# Roland_mem3.net
KiCad netlist of a schematic drawn in EAGLE
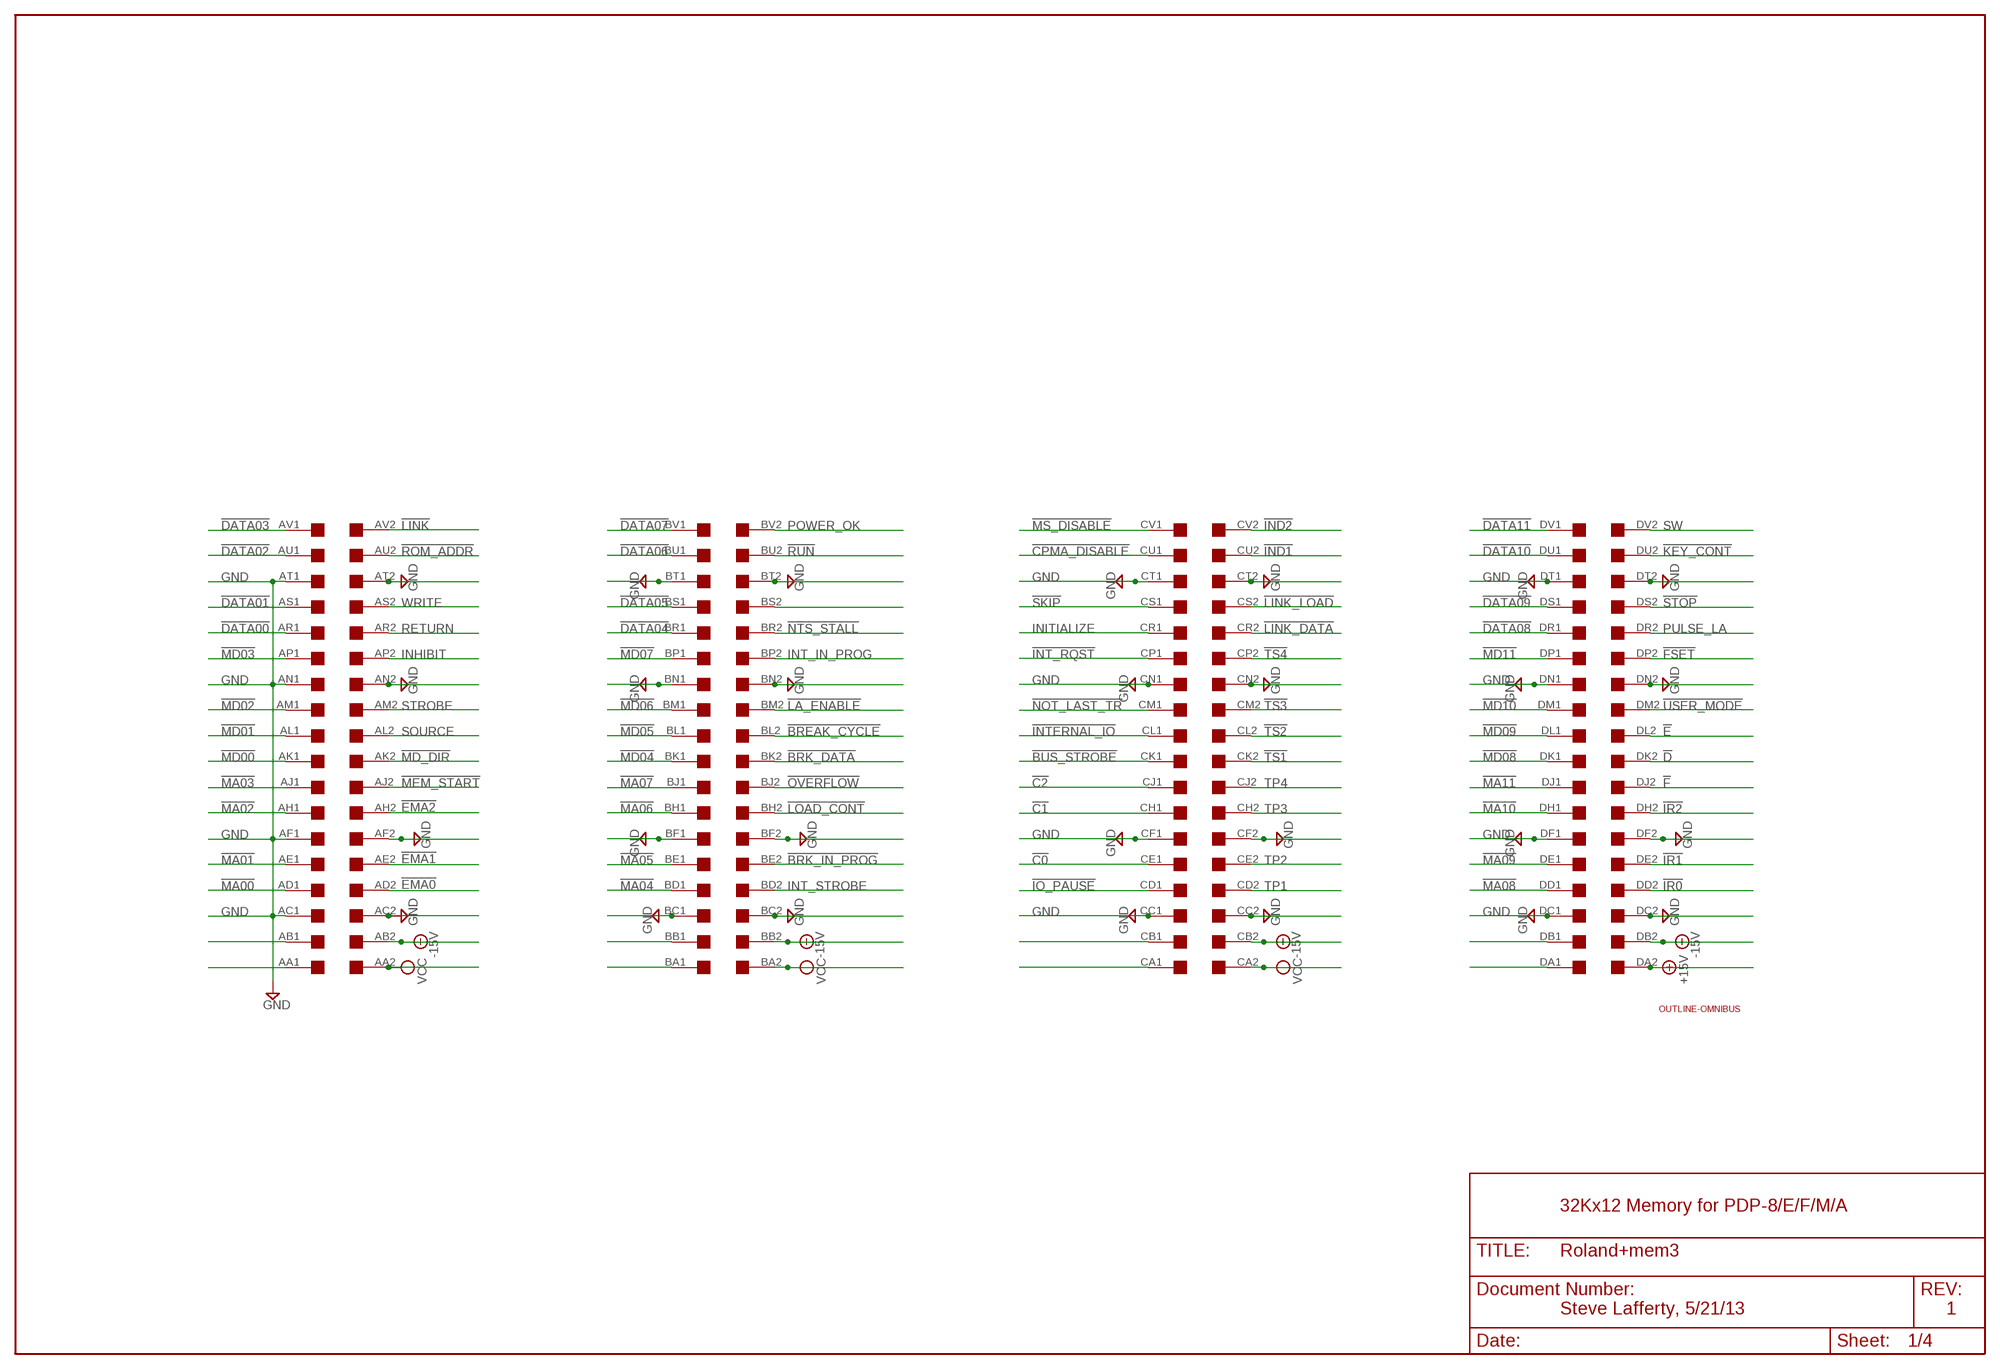
[diagram p0: schematic, sheet 1]
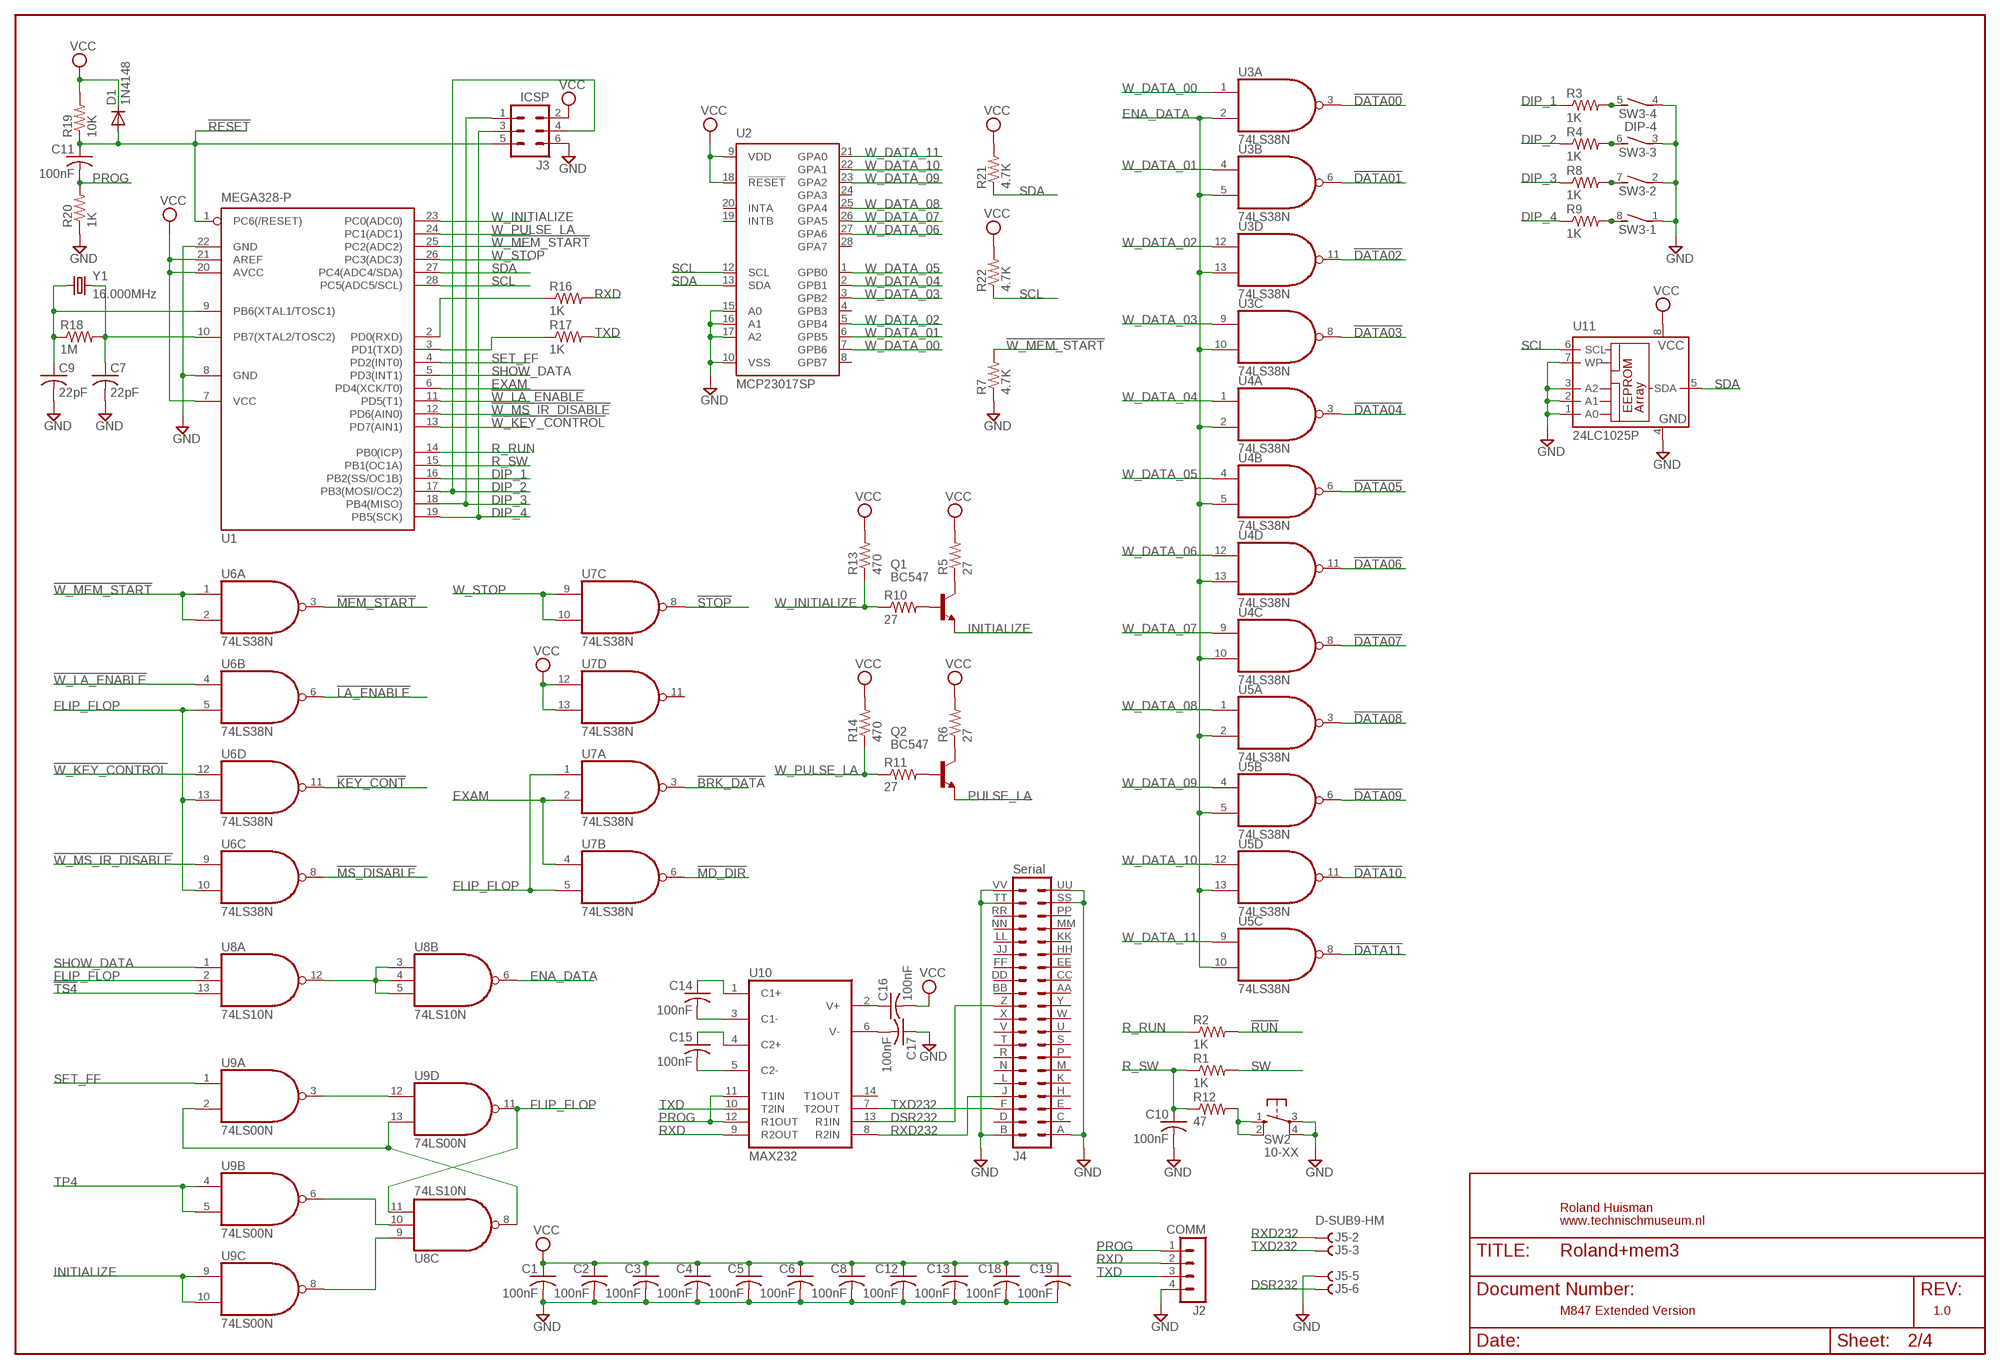
[diagram p1: schematic, sheet 2]
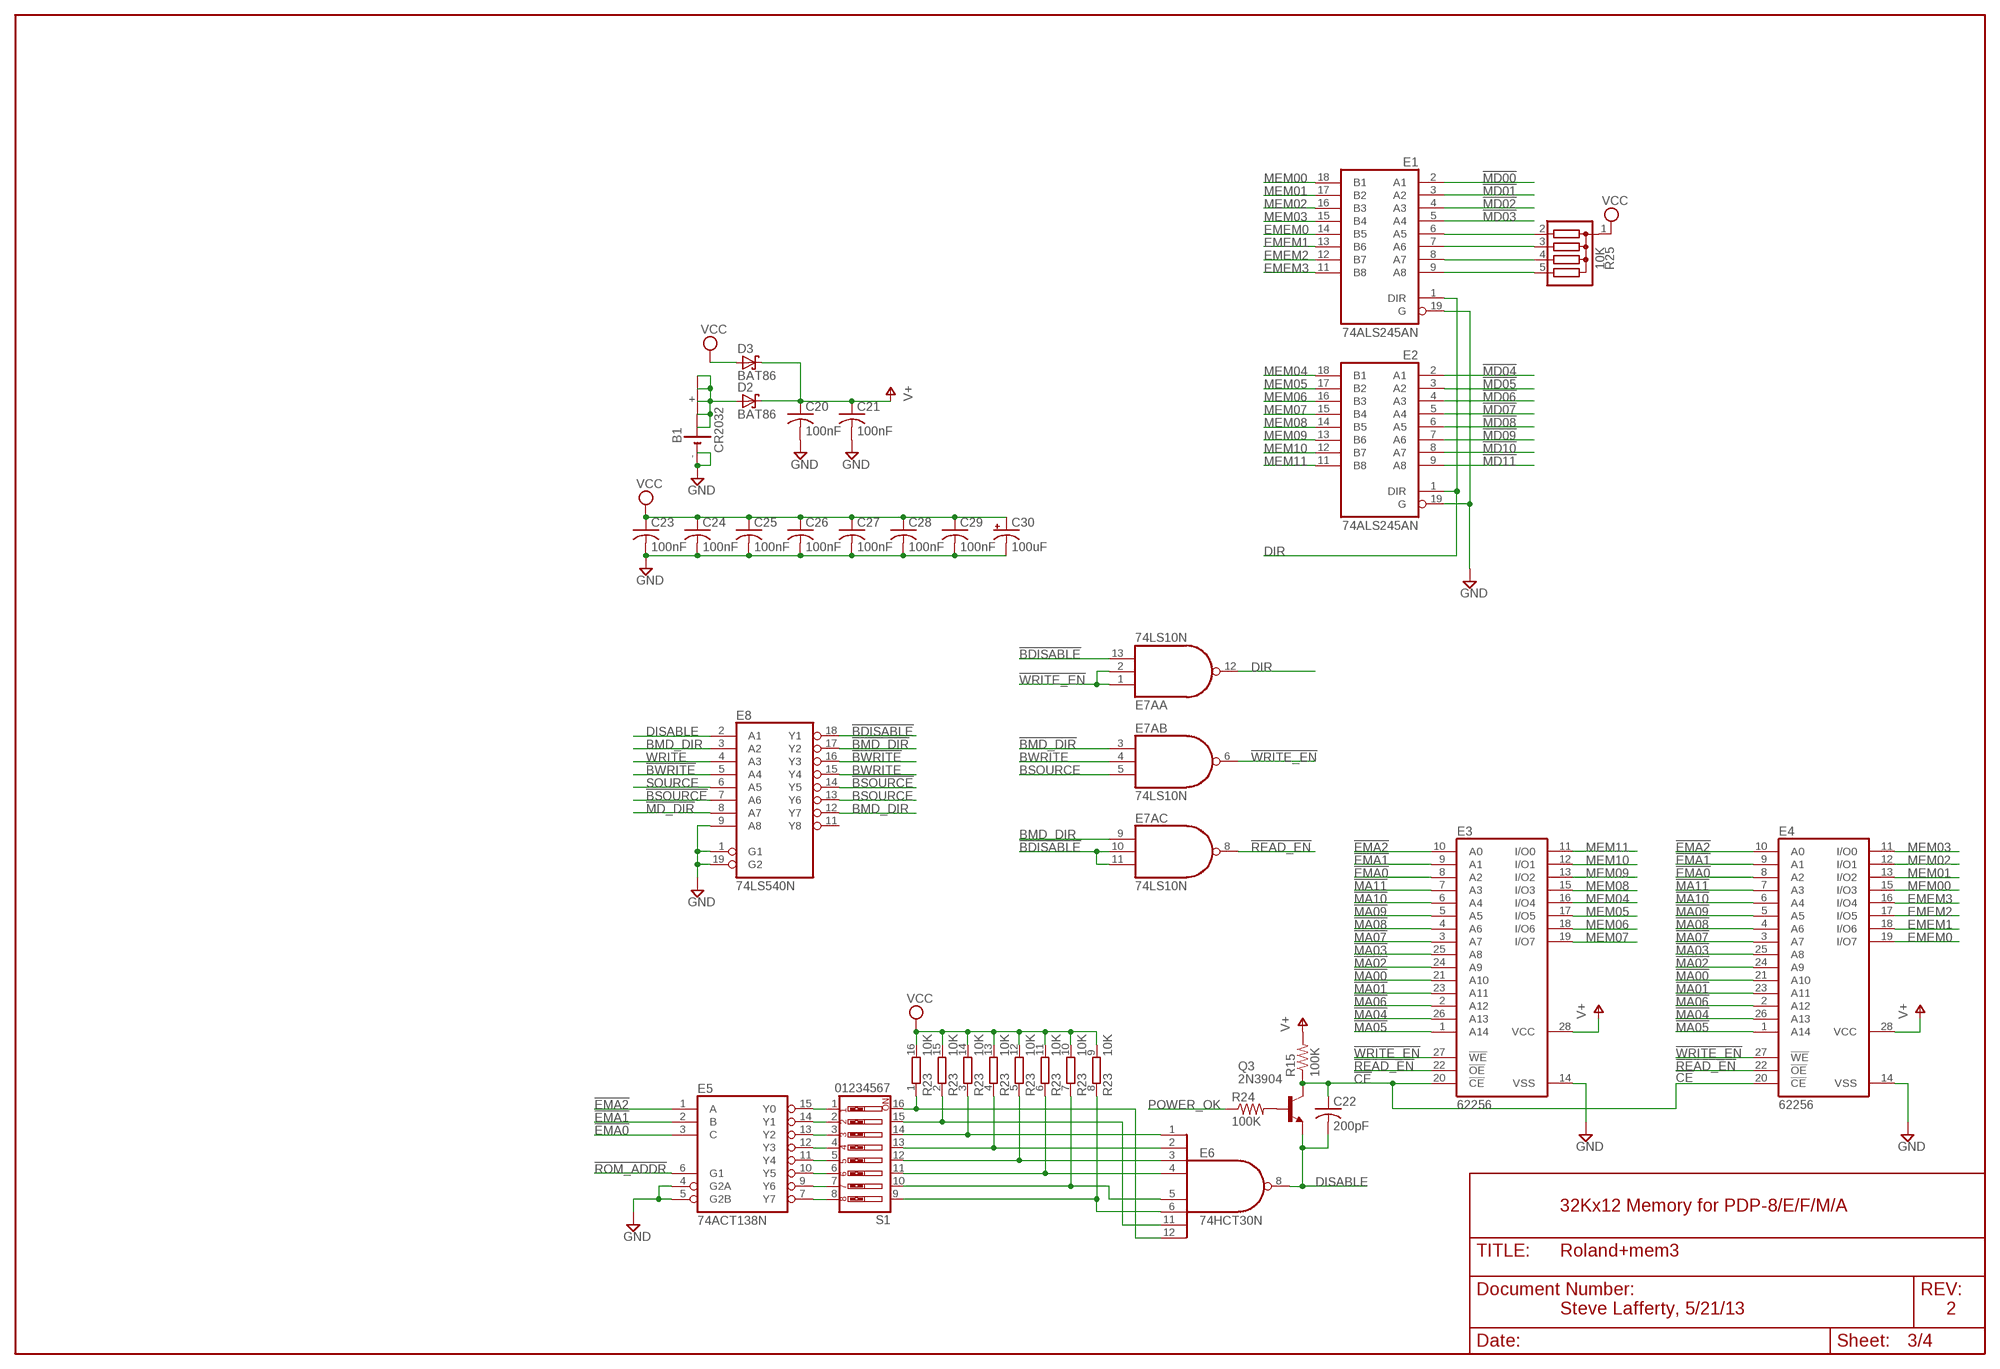
[diagram p2: schematic, sheet 3]
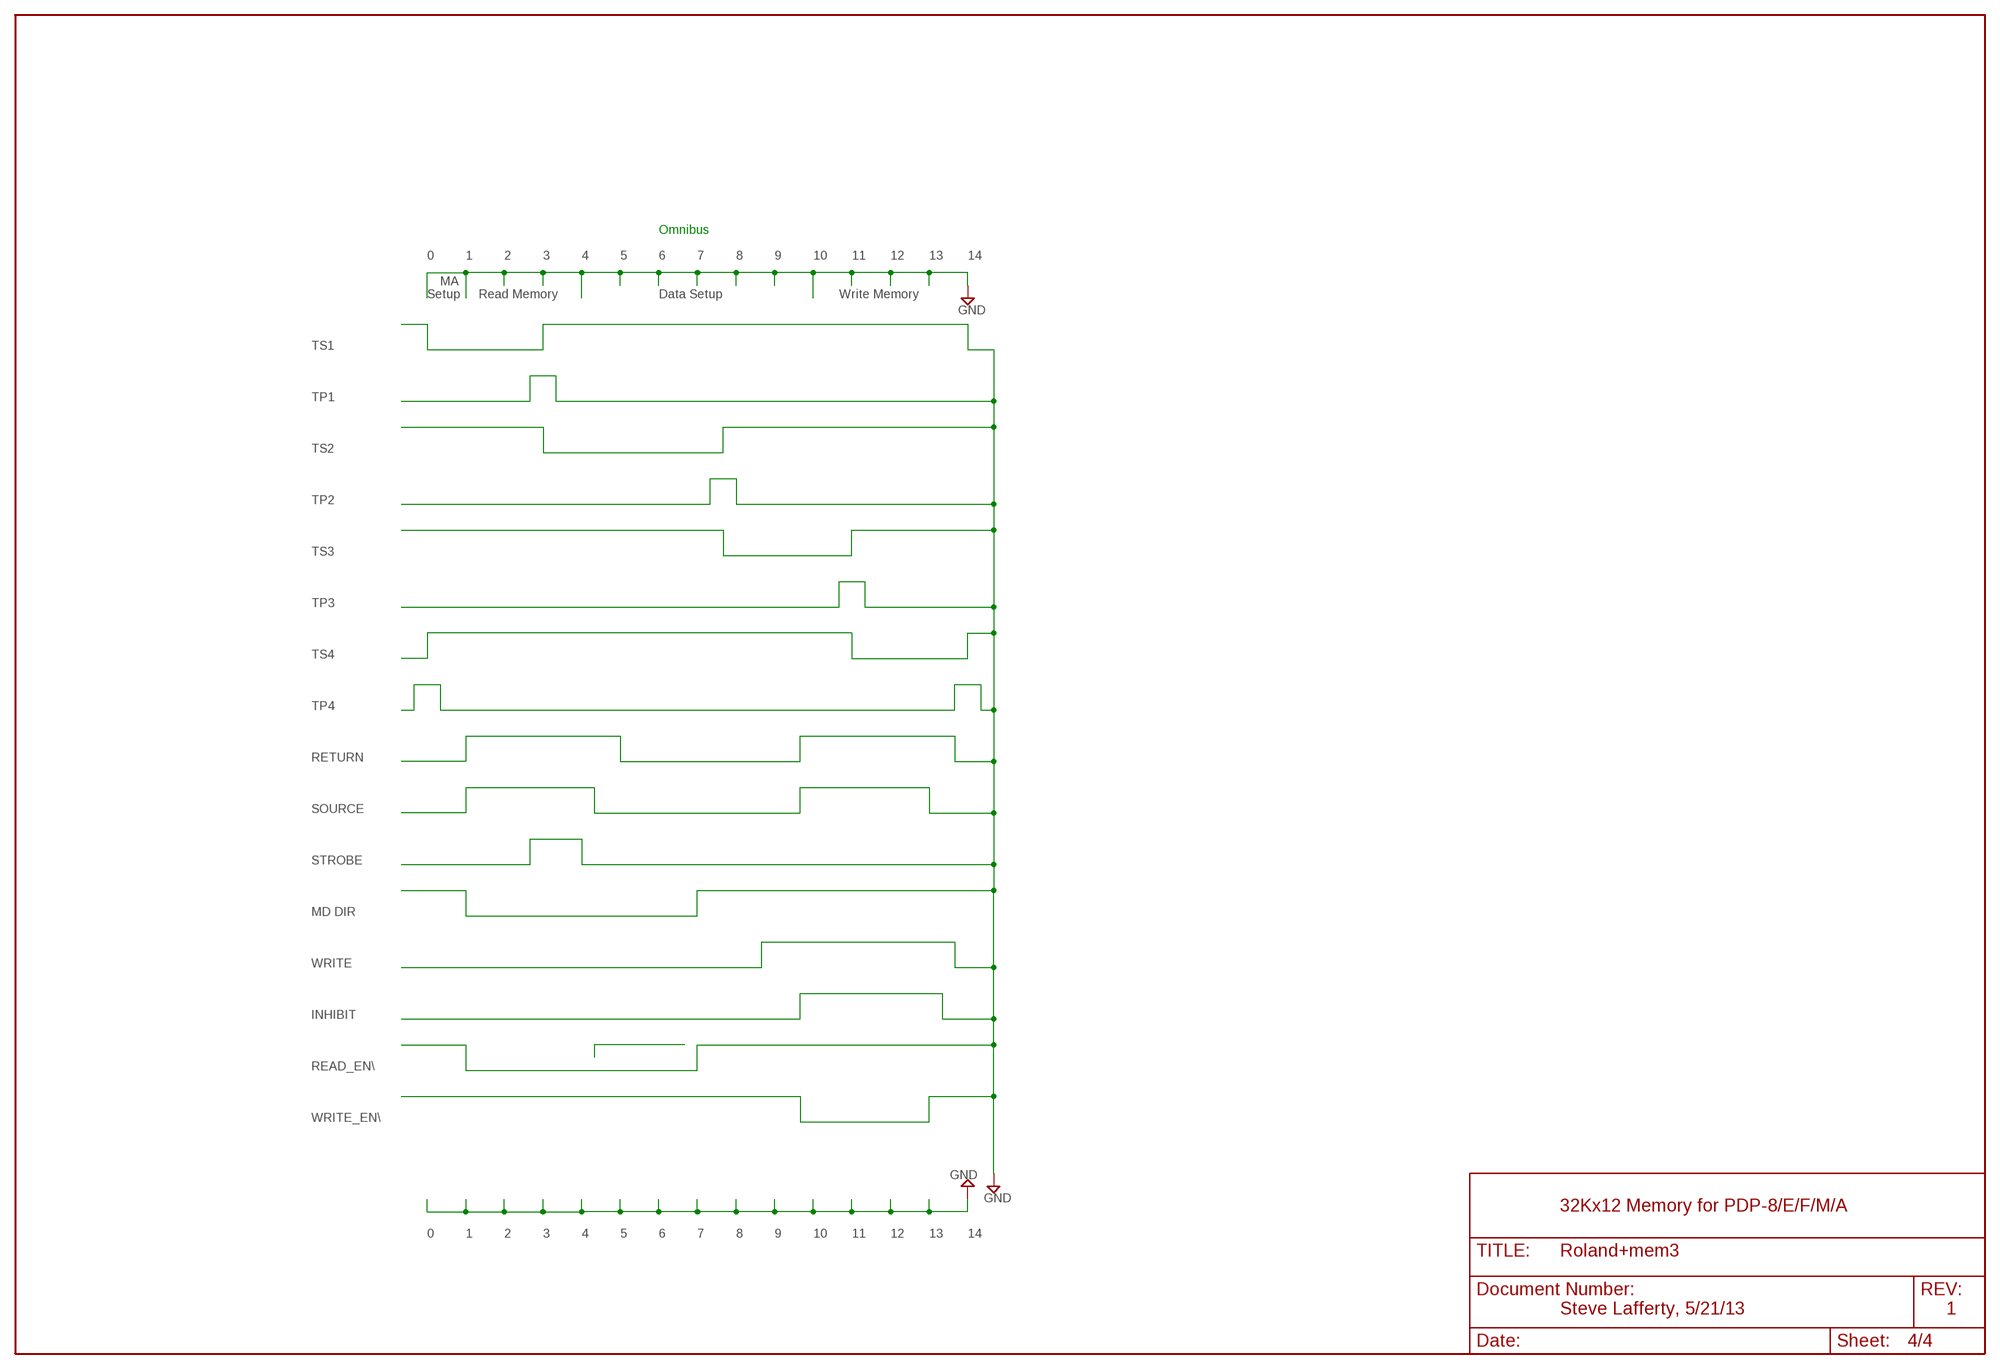
[diagram p3: schematic, sheet 4]

(export (version "E")
  (design (tool "Eeschema 10.0.6"))
  (components
    (comp (ref "J1")
      (value "EDGE")
      (footprint "eagle-import:EDGE-CON8")
      (libsource (lib "eagle-import") (part "QUAD"))
    )
    (comp (ref "U$1")
      (value "OUTLINE-OMNIBUS")
      (footprint "eagle-import:OMNIBUS")
      (libsource (lib "eagle-import") (part "OUTLINE-OMNIBUS"))
    )
    (comp (ref "C1")
      (value "100nF")
      (footprint "eagle-import:C050-025X075")
      (libsource (lib "eagle-import") (part "C-US050-025X075"))
    )
    (comp (ref "C2")
      (value "100nF")
      (footprint "eagle-import:C050-025X075")
      (libsource (lib "eagle-import") (part "C-US050-025X075"))
    )
    (comp (ref "C3")
      (value "100nF")
      (footprint "eagle-import:C050-025X075")
      (libsource (lib "eagle-import") (part "C-US050-025X075"))
    )
    (comp (ref "C4")
      (value "100nF")
      (footprint "eagle-import:C050-025X075")
      (libsource (lib "eagle-import") (part "C-US050-025X075"))
    )
    (comp (ref "C5")
      (value "100nF")
      (footprint "eagle-import:C050-025X075")
      (libsource (lib "eagle-import") (part "C-US050-025X075"))
    )
    (comp (ref "C6")
      (value "100nF")
      (footprint "eagle-import:C050-025X075")
      (libsource (lib "eagle-import") (part "C-US050-025X075"))
    )
    (comp (ref "C7")
      (value "22pF")
      (footprint "eagle-import:C050-025X075")
      (libsource (lib "eagle-import") (part "C-US050-025X075"))
    )
    (comp (ref "C8")
      (value "100nF")
      (footprint "eagle-import:C050-025X075")
      (libsource (lib "eagle-import") (part "C-US050-025X075"))
    )
    (comp (ref "C9")
      (value "22pF")
      (footprint "eagle-import:C050-025X075")
      (libsource (lib "eagle-import") (part "C-US050-025X075"))
    )
    (comp (ref "C10")
      (value "100nF")
      (footprint "eagle-import:C050-025X075")
      (libsource (lib "eagle-import") (part "C-US050-025X075"))
    )
    (comp (ref "C11")
      (value "100nF")
      (footprint "eagle-import:C050-025X075")
      (libsource (lib "eagle-import") (part "C-US050-025X075"))
    )
    (comp (ref "C12")
      (value "100nF")
      (footprint "eagle-import:C050-025X075")
      (libsource (lib "eagle-import") (part "C-US050-025X075"))
    )
    (comp (ref "C13")
      (value "100nF")
      (footprint "eagle-import:C050-025X075")
      (libsource (lib "eagle-import") (part "C-US050-025X075"))
    )
    (comp (ref "C14")
      (value "100nF")
      (footprint "eagle-import:C050-025X075")
      (libsource (lib "eagle-import") (part "C-US050-025X075"))
    )
    (comp (ref "C15")
      (value "100nF")
      (footprint "eagle-import:C050-025X075")
      (libsource (lib "eagle-import") (part "C-US050-025X075"))
    )
    (comp (ref "C16")
      (value "100nF")
      (footprint "eagle-import:C050-025X075")
      (libsource (lib "eagle-import") (part "C-US050-025X075"))
    )
    (comp (ref "C17")
      (value "100nF")
      (footprint "eagle-import:C050-025X075")
      (libsource (lib "eagle-import") (part "C-US050-025X075"))
    )
    (comp (ref "C18")
      (value "100nF")
      (footprint "eagle-import:C050-025X075")
      (libsource (lib "eagle-import") (part "C-US050-025X075"))
    )
    (comp (ref "C19")
      (value "100nF")
      (footprint "eagle-import:C050-025X075")
      (libsource (lib "eagle-import") (part "C-US050-025X075"))
    )
    (comp (ref "D1")
      (value "1N4148")
      (footprint "eagle-import:DO35-10")
      (libsource (lib "eagle-import") (part "1N4148DO35-10"))
    )
    (comp (ref "J2")
      (value "COMM")
      (footprint "eagle-import:MA04-1")
      (libsource (lib "eagle-import") (part "MA04-1"))
    )
    (comp (ref "J3")
      (value "ICSP")
      (footprint "eagle-import:MA03-2")
      (libsource (lib "eagle-import") (part "MA03-2"))
    )
    (comp (ref "J4")
      (value "Serial")
      (footprint "eagle-import:DEC40PINH")
      (libsource (lib "eagle-import") (part "DEC40PINH"))
    )
    (comp (ref "J5")
      (value "D-SUB9-HM")
      (footprint "eagle-import:H5M09RA")
      (libsource (lib "eagle-import") (part "D-SUB9-H5M09RA"))
    )
    (comp (ref "Q1")
      (value "BC547")
      (footprint "eagle-import:TO5")
      (libsource (lib "eagle-import") (part "-NPN-TO5"))
    )
    (comp (ref "Q2")
      (value "BC547")
      (footprint "eagle-import:TO5")
      (libsource (lib "eagle-import") (part "-NPN-TO5"))
    )
    (comp (ref "R1")
      (value "1K")
      (footprint "eagle-import:0207_10")
      (libsource (lib "eagle-import") (part "R-US_0207/10"))
    )
    (comp (ref "R2")
      (value "1K")
      (footprint "eagle-import:0207_10")
      (libsource (lib "eagle-import") (part "R-US_0207/10"))
    )
    (comp (ref "R3")
      (value "1K")
      (footprint "eagle-import:0207_10")
      (libsource (lib "eagle-import") (part "R-US_0207/10"))
    )
    (comp (ref "R4")
      (value "1K")
      (footprint "eagle-import:0207_10")
      (libsource (lib "eagle-import") (part "R-US_0207/10"))
    )
    (comp (ref "R5")
      (value "27")
      (footprint "eagle-import:0207_10")
      (libsource (lib "eagle-import") (part "R-US_0207/10"))
    )
    (comp (ref "R6")
      (value "27")
      (footprint "eagle-import:0207_10")
      (libsource (lib "eagle-import") (part "R-US_0207/10"))
    )
    (comp (ref "R7")
      (value "4.7K")
      (footprint "eagle-import:0207_10")
      (libsource (lib "eagle-import") (part "R-US_0207/10"))
    )
    (comp (ref "R8")
      (value "1K")
      (footprint "eagle-import:0207_10")
      (libsource (lib "eagle-import") (part "R-US_0207/10"))
    )
    (comp (ref "R9")
      (value "1K")
      (footprint "eagle-import:0207_10")
      (libsource (lib "eagle-import") (part "R-US_0207/10"))
    )
    (comp (ref "R10")
      (value "27")
      (footprint "eagle-import:0207_10")
      (libsource (lib "eagle-import") (part "R-US_0207/10"))
    )
    (comp (ref "R11")
      (value "27")
      (footprint "eagle-import:0207_10")
      (libsource (lib "eagle-import") (part "R-US_0207/10"))
    )
    (comp (ref "R12")
      (value "47")
      (footprint "eagle-import:0207_10")
      (libsource (lib "eagle-import") (part "R-US_0207/10"))
    )
    (comp (ref "R13")
      (value "470")
      (footprint "eagle-import:0207_10")
      (libsource (lib "eagle-import") (part "R-US_0207/10"))
    )
    (comp (ref "R14")
      (value "470")
      (footprint "eagle-import:0207_10")
      (libsource (lib "eagle-import") (part "R-US_0207/10"))
    )
    (comp (ref "R16")
      (value "1K")
      (footprint "eagle-import:0207_10")
      (libsource (lib "eagle-import") (part "R-US_0207/10"))
    )
    (comp (ref "R17")
      (value "1K")
      (footprint "eagle-import:0207_10")
      (libsource (lib "eagle-import") (part "R-US_0207/10"))
    )
    (comp (ref "R18")
      (value "1M")
      (footprint "eagle-import:0207_10")
      (libsource (lib "eagle-import") (part "R-US_0207/10"))
    )
    (comp (ref "R19")
      (value "10K")
      (footprint "eagle-import:0207_10")
      (libsource (lib "eagle-import") (part "R-US_0207/10"))
    )
    (comp (ref "R20")
      (value "1K")
      (footprint "eagle-import:0207_10")
      (libsource (lib "eagle-import") (part "R-US_0207/10"))
    )
    (comp (ref "R21")
      (value "4.7K")
      (footprint "eagle-import:0207_10")
      (libsource (lib "eagle-import") (part "R-US_0207/10"))
    )
    (comp (ref "R22")
      (value "4.7K")
      (footprint "eagle-import:0207_10")
      (libsource (lib "eagle-import") (part "R-US_0207/10"))
    )
    (comp (ref "SW2")
      (value "10-XX")
      (footprint "eagle-import:B3F-10XX")
      (fields (field (name "MPN") "B3F-1000"))
      (libsource (lib "eagle-import") (part "10-XX"))
    )
    (comp (ref "SW3")
      (value "DIP-4")
      (footprint "eagle-import:DIP04S")
      (libsource (lib "eagle-import") (part "DIP04S"))
    )
    (comp (ref "U1")
      (value "MEGA328-P")
      (footprint "eagle-import:DIL28-3")
      (libsource (lib "eagle-import") (part "MEGA8-P"))
    )
    (comp (ref "U2")
      (value "MCP23017SP")
      (footprint "eagle-import:DIL28-3")
      (fields (field (name "MF") "MICROCHIP") (field (name "MPN") "MCP23017-E/SP"))
      (libsource (lib "eagle-import") (part "MCP23017SP"))
    )
    (comp (ref "U3")
      (value "74LS38N")
      (footprint "eagle-import:DIL14")
      (libsource (lib "eagle-import") (part "7438NLS"))
    )
    (comp (ref "U4")
      (value "74LS38N")
      (footprint "eagle-import:DIL14")
      (libsource (lib "eagle-import") (part "7438NLS"))
    )
    (comp (ref "U5")
      (value "74LS38N")
      (footprint "eagle-import:DIL14")
      (libsource (lib "eagle-import") (part "7438NLS"))
    )
    (comp (ref "U6")
      (value "74LS38N")
      (footprint "eagle-import:DIL14")
      (libsource (lib "eagle-import") (part "7438NLS"))
    )
    (comp (ref "U7")
      (value "74LS38N")
      (footprint "eagle-import:DIL14")
      (libsource (lib "eagle-import") (part "7438NLS"))
    )
    (comp (ref "U8")
      (value "74LS10N")
      (footprint "eagle-import:DIL14")
      (libsource (lib "eagle-import") (part "7410NLS"))
    )
    (comp (ref "U9")
      (value "74LS00N")
      (footprint "eagle-import:DIL14")
      (libsource (lib "eagle-import") (part "7400NLS"))
    )
    (comp (ref "U10")
      (value "MAX232")
      (footprint "eagle-import:DIL16")
      (fields (field (name "MF") "MAXIM") (field (name "MPN") "MAX232ACPE+"))
      (libsource (lib "eagle-import") (part "MAX232"))
    )
    (comp (ref "U11")
      (value "24LC1025P")
      (footprint "eagle-import:DIL8")
      (fields (field (name "MF") "MICROCHIP") (field (name "MPN") "24LC025-I/P"))
      (libsource (lib "eagle-import") (part "24PLC025"))
    )
    (comp (ref "Y1")
      (value "16.000MHz")
      (footprint "eagle-import:HC49U-H")
      (libsource (lib "eagle-import") (part "CRYSTALHC49U-H"))
    )
    (comp (ref "B1")
      (value "CR2032")
      (footprint "eagle-import:B2430UNI")
      (libsource (lib "eagle-import") (part "B2430UNI"))
    )
    (comp (ref "C20")
      (value "100nF")
      (footprint "eagle-import:C050-025X075")
      (libsource (lib "eagle-import") (part "C-US050-025X075"))
    )
    (comp (ref "C21")
      (value "100nF")
      (footprint "eagle-import:C050-025X075")
      (libsource (lib "eagle-import") (part "C-US050-025X075"))
    )
    (comp (ref "C22")
      (value "200pF")
      (footprint "eagle-import:C050-025X075")
      (libsource (lib "eagle-import") (part "C-US050-025X075"))
    )
    (comp (ref "C23")
      (value "100nF")
      (footprint "eagle-import:C050-025X075")
      (libsource (lib "eagle-import") (part "C-US050-025X075"))
    )
    (comp (ref "C24")
      (value "100nF")
      (footprint "eagle-import:C050-025X075")
      (libsource (lib "eagle-import") (part "C-US050-025X075"))
    )
    (comp (ref "C25")
      (value "100nF")
      (footprint "eagle-import:C050-025X075")
      (libsource (lib "eagle-import") (part "C-US050-025X075"))
    )
    (comp (ref "C26")
      (value "100nF")
      (footprint "eagle-import:C050-025X075")
      (libsource (lib "eagle-import") (part "C-US050-025X075"))
    )
    (comp (ref "C27")
      (value "100nF")
      (footprint "eagle-import:C050-025X075")
      (libsource (lib "eagle-import") (part "C-US050-025X075"))
    )
    (comp (ref "C28")
      (value "100nF")
      (footprint "eagle-import:C050-025X075")
      (libsource (lib "eagle-import") (part "C-US050-025X075"))
    )
    (comp (ref "C29")
      (value "100nF")
      (footprint "eagle-import:C050-025X075")
      (libsource (lib "eagle-import") (part "C-US050-025X075"))
    )
    (comp (ref "C30")
      (value "100uF")
      (footprint "eagle-import:E12-8")
      (libsource (lib "eagle-import") (part "CPOL-USE20-8AXIAL"))
    )
    (comp (ref "D2")
      (value "BAT86")
      (footprint "eagle-import:DO35-10")
      (libsource (lib "eagle-import") (part "BAT19"))
    )
    (comp (ref "D3")
      (value "BAT86")
      (footprint "eagle-import:DO35-10")
      (libsource (lib "eagle-import") (part "BAT19"))
    )
    (comp (ref "E1")
      (value "74ALS245AN")
      (footprint "eagle-import:DIL20")
      (libsource (lib "eagle-import") (part "74245NLS"))
    )
    (comp (ref "E2")
      (value "74ALS245AN")
      (footprint "eagle-import:DIL20")
      (libsource (lib "eagle-import") (part "74245NLS"))
    )
    (comp (ref "E3")
      (value "62256")
      (footprint "eagle-import:DIL28-6")
      (libsource (lib "eagle-import") (part "58C256P"))
    )
    (comp (ref "E4")
      (value "62256")
      (footprint "eagle-import:DIL28-6")
      (libsource (lib "eagle-import") (part "58C256P"))
    )
    (comp (ref "E5")
      (value "74ACT138N")
      (footprint "eagle-import:DIL16")
      (libsource (lib "eagle-import") (part "74138NLS"))
    )
    (comp (ref "E6")
      (value "74HCT30N")
      (footprint "eagle-import:DIL14")
      (libsource (lib "eagle-import") (part "7430NLS"))
    )
    (comp (ref "E7A")
      (value "74LS10N")
      (footprint "eagle-import:DIL14")
      (libsource (lib "eagle-import") (part "7410NLS"))
    )
    (comp (ref "E8")
      (value "74LS540N")
      (footprint "eagle-import:DIL20")
      (libsource (lib "eagle-import") (part "74540NLS"))
    )
    (comp (ref "Q3")
      (value "2N3904")
      (footprint "eagle-import:TO92")
      (libsource (lib "eagle-import") (part "2N3904"))
    )
    (comp (ref "R15")
      (value "100K")
      (footprint "eagle-import:0207_10")
      (libsource (lib "eagle-import") (part "R-US_0207/10"))
    )
    (comp (ref "R23")
      (value "10K")
      (footprint "eagle-import:DIL16")
      (libsource (lib "eagle-import") (part "8R-P"))
    )
    (comp (ref "R24")
      (value "100K")
      (footprint "eagle-import:0207_10")
      (libsource (lib "eagle-import") (part "R-US_0207/10"))
    )
    (comp (ref "R25")
      (value "10K")
      (footprint "eagle-import:SIL5")
      (libsource (lib "eagle-import") (part "G04R"))
    )
    (comp (ref "S1")
      (value "01234567")
      (footprint "eagle-import:EDG-08")
      (libsource (lib "eagle-import") (part "SW_DIP-8"))
    )
  )
  (nets
    (net (code "1") (name "+15V") (class "Default")
      (node (ref "J1") (pin "DA2") (pinfunction "1_DA2") (pintype "bidirectional"))
    )
    (net (code "2") (name "-15V") (class "Default")
      (node (ref "J1") (pin "AB2") (pinfunction "1_AB2") (pintype "bidirectional"))
      (node (ref "J1") (pin "BB2") (pinfunction "1_BB2") (pintype "bidirectional"))
      (node (ref "J1") (pin "CB2") (pinfunction "1_CB2") (pintype "bidirectional"))
      (node (ref "J1") (pin "DB2") (pinfunction "1_DB2") (pintype "bidirectional"))
    )
    (net (code "3") (name "BMD_DIR") (class "Default")
      (node (ref "E7A") (pin "9") (pinfunction "I0_9") (pintype "input"))
      (node (ref "E8") (pin "12") (pinfunction "Y7_12") (pintype "tri_state"))
      (node (ref "E8") (pin "3") (pinfunction "A2_3") (pintype "input"))
    )
    (net (code "4") (name "BSOURCE") (class "Default")
      (node (ref "E7A") (pin "5") (pinfunction "I2_5") (pintype "input"))
      (node (ref "E8") (pin "13") (pinfunction "Y6_13") (pintype "tri_state"))
    )
    (net (code "5") (name "BWRITE") (class "Default")
      (node (ref "E7A") (pin "4") (pinfunction "I1_4") (pintype "input"))
      (node (ref "E8") (pin "15") (pinfunction "Y4_15") (pintype "tri_state"))
    )
    (net (code "6") (name "DIP_1") (class "Default")
      (node (ref "R3") (pin "1") (pinfunction "1_1") (pintype "passive"))
      (node (ref "U1") (pin "16") (pinfunction "PB2(SS/OC1B)_16") (pintype "bidirectional"))
    )
    (net (code "7") (name "DIP_2") (class "Default")
      (node (ref "J3") (pin "4") (pinfunction "4_4") (pintype "passive"))
      (node (ref "R4") (pin "1") (pinfunction "1_1") (pintype "passive"))
      (node (ref "U1") (pin "17") (pinfunction "PB3(MOSI/OC2)_17") (pintype "bidirectional"))
    )
    (net (code "8") (name "DIP_3") (class "Default")
      (node (ref "J3") (pin "1") (pinfunction "1_1") (pintype "passive"))
      (node (ref "R8") (pin "1") (pinfunction "1_1") (pintype "passive"))
      (node (ref "U1") (pin "18") (pinfunction "PB4(MISO)_18") (pintype "bidirectional"))
    )
    (net (code "9") (name "DIP_4") (class "Default")
      (node (ref "J3") (pin "3") (pinfunction "3_3") (pintype "passive"))
      (node (ref "R9") (pin "1") (pinfunction "1_1") (pintype "passive"))
      (node (ref "U1") (pin "19") (pinfunction "PB5(SCK)_19") (pintype "bidirectional"))
    )
    (net (code "10") (name "DIR") (class "Default")
      (node (ref "E1") (pin "1") (pinfunction "DIR_1") (pintype "input"))
      (node (ref "E2") (pin "1") (pinfunction "DIR_1") (pintype "input"))
      (node (ref "E7A") (pin "12") (pinfunction "O_12") (pintype "output"))
    )
    (net (code "11") (name "DISABLE") (class "Default")
      (node (ref "C22") (pin "2") (pinfunction "2_2") (pintype "passive"))
      (node (ref "E6") (pin "8") (pinfunction "O_8") (pintype "output"))
      (node (ref "E8") (pin "2") (pinfunction "A1_2") (pintype "input"))
      (node (ref "Q3") (pin "3") (pinfunction "E_3") (pintype "passive"))
    )
    (net (code "12") (name "DSR232") (class "Default")
      (node (ref "J4") (pin "Z") (pinfunction "22_Z") (pintype "bidirectional"))
      (node (ref "J5") (pin "6") (pinfunction "F_6") (pintype "passive"))
      (node (ref "U10") (pin "13") (pinfunction "R1IN_13") (pintype "input"))
    )
    (net (code "13") (name "EMEM0") (class "Default")
      (node (ref "E1") (pin "14") (pinfunction "B5_14") (pintype "bidirectional"))
      (node (ref "E4") (pin "19") (pinfunction "I/O7_19") (pintype "tri_state"))
    )
    (net (code "14") (name "EMEM1") (class "Default")
      (node (ref "E1") (pin "13") (pinfunction "B6_13") (pintype "bidirectional"))
      (node (ref "E4") (pin "18") (pinfunction "I/O6_18") (pintype "tri_state"))
    )
    (net (code "15") (name "EMEM2") (class "Default")
      (node (ref "E1") (pin "12") (pinfunction "B7_12") (pintype "bidirectional"))
      (node (ref "E4") (pin "17") (pinfunction "I/O5_17") (pintype "tri_state"))
    )
    (net (code "16") (name "EMEM3") (class "Default")
      (node (ref "E1") (pin "11") (pinfunction "B8_11") (pintype "bidirectional"))
      (node (ref "E4") (pin "16") (pinfunction "I/O4_16") (pintype "tri_state"))
    )
    (net (code "17") (name "ENA_DATA") (class "Default")
      (node (ref "U3") (pin "10") (pinfunction "I1_10") (pintype "input"))
      (node (ref "U3") (pin "13") (pinfunction "I1_13") (pintype "input"))
      (node (ref "U3") (pin "2") (pinfunction "I1_2") (pintype "input"))
      (node (ref "U3") (pin "5") (pinfunction "I1_5") (pintype "input"))
      (node (ref "U4") (pin "10") (pinfunction "I1_10") (pintype "input"))
      (node (ref "U4") (pin "13") (pinfunction "I1_13") (pintype "input"))
      (node (ref "U4") (pin "2") (pinfunction "I1_2") (pintype "input"))
      (node (ref "U4") (pin "5") (pinfunction "I1_5") (pintype "input"))
      (node (ref "U5") (pin "10") (pinfunction "I1_10") (pintype "input"))
      (node (ref "U5") (pin "13") (pinfunction "I1_13") (pintype "input"))
      (node (ref "U5") (pin "2") (pinfunction "I1_2") (pintype "input"))
      (node (ref "U5") (pin "5") (pinfunction "I1_5") (pintype "input"))
      (node (ref "U8") (pin "6") (pinfunction "O_6") (pintype "output"))
    )
    (net (code "18") (name "EXAM") (class "Default")
      (node (ref "U1") (pin "6") (pinfunction "PD4(XCK/T0)_6") (pintype "bidirectional"))
      (node (ref "U7") (pin "2") (pinfunction "I1_2") (pintype "input"))
      (node (ref "U7") (pin "4") (pinfunction "I0_4") (pintype "input"))
    )
    (net (code "19") (name "FLIP_FLOP") (class "Default")
      (node (ref "U6") (pin "10") (pinfunction "I1_10") (pintype "input"))
      (node (ref "U6") (pin "13") (pinfunction "I1_13") (pintype "input"))
      (node (ref "U6") (pin "5") (pinfunction "I1_5") (pintype "input"))
      (node (ref "U7") (pin "1") (pinfunction "I0_1") (pintype "input"))
      (node (ref "U7") (pin "5") (pinfunction "I1_5") (pintype "input"))
      (node (ref "U8") (pin "11") (pinfunction "I2_11") (pintype "input"))
      (node (ref "U8") (pin "2") (pinfunction "I1_2") (pintype "input"))
      (node (ref "U9") (pin "11") (pinfunction "O_11") (pintype "output"))
    )
    (net (code "20") (name "GND") (class "Default")
      (node (ref "B1") (pin "-") (pinfunction "-_-") (pintype "passive"))
      (node (ref "B1") (pin "-@1") (pinfunction "-_-@1") (pintype "passive"))
      (node (ref "C1") (pin "2") (pinfunction "2_2") (pintype "passive"))
      (node (ref "C10") (pin "2") (pinfunction "2_2") (pintype "passive"))
      (node (ref "C12") (pin "2") (pinfunction "2_2") (pintype "passive"))
      (node (ref "C13") (pin "2") (pinfunction "2_2") (pintype "passive"))
      (node (ref "C17") (pin "1") (pinfunction "1_1") (pintype "passive"))
      (node (ref "C18") (pin "2") (pinfunction "2_2") (pintype "passive"))
      (node (ref "C19") (pin "2") (pinfunction "2_2") (pintype "passive"))
      (node (ref "C2") (pin "2") (pinfunction "2_2") (pintype "passive"))
      (node (ref "C20") (pin "2") (pinfunction "2_2") (pintype "passive"))
      (node (ref "C21") (pin "2") (pinfunction "2_2") (pintype "passive"))
      (node (ref "C23") (pin "2") (pinfunction "2_2") (pintype "passive"))
      (node (ref "C24") (pin "2") (pinfunction "2_2") (pintype "passive"))
      (node (ref "C25") (pin "2") (pinfunction "2_2") (pintype "passive"))
      (node (ref "C26") (pin "2") (pinfunction "2_2") (pintype "passive"))
      (node (ref "C27") (pin "2") (pinfunction "2_2") (pintype "passive"))
      (node (ref "C28") (pin "2") (pinfunction "2_2") (pintype "passive"))
      (node (ref "C29") (pin "2") (pinfunction "2_2") (pintype "passive"))
      (node (ref "C3") (pin "2") (pinfunction "2_2") (pintype "passive"))
      (node (ref "C30") (pin "-") (pinfunction "-_-") (pintype "passive"))
      (node (ref "C4") (pin "2") (pinfunction "2_2") (pintype "passive"))
      (node (ref "C5") (pin "2") (pinfunction "2_2") (pintype "passive"))
      (node (ref "C6") (pin "2") (pinfunction "2_2") (pintype "passive"))
      (node (ref "C7") (pin "2") (pinfunction "2_2") (pintype "passive"))
      (node (ref "C8") (pin "2") (pinfunction "2_2") (pintype "passive"))
      (node (ref "C9") (pin "2") (pinfunction "2_2") (pintype "passive"))
      (node (ref "E1") (pin "19") (pinfunction "G_19") (pintype "input"))
      (node (ref "E2") (pin "19") (pinfunction "G_19") (pintype "input"))
      (node (ref "E3") (pin "14") (pinfunction "VSS_14") (pintype "power_in"))
      (node (ref "E4") (pin "14") (pinfunction "VSS_14") (pintype "power_in"))
      (node (ref "E5") (pin "4") (pinfunction "G2A_4") (pintype "input"))
      (node (ref "E5") (pin "5") (pinfunction "G2B_5") (pintype "input"))
      (node (ref "E8") (pin "1") (pinfunction "G1_1") (pintype "input"))
      (node (ref "E8") (pin "19") (pinfunction "G2_19") (pintype "input"))
      (node (ref "E8") (pin "9") (pinfunction "A8_9") (pintype "input"))
      (node (ref "J1") (pin "AC1") (pinfunction "1_AC1") (pintype "bidirectional"))
      (node (ref "J1") (pin "AC2") (pinfunction "1_AC2") (pintype "bidirectional"))
      (node (ref "J1") (pin "AF1") (pinfunction "1_AF1") (pintype "bidirectional"))
      (node (ref "J1") (pin "AF2") (pinfunction "1_AF2") (pintype "bidirectional"))
      (node (ref "J1") (pin "AN1") (pinfunction "1_AN1") (pintype "bidirectional"))
      (node (ref "J1") (pin "AN2") (pinfunction "1_AN2") (pintype "bidirectional"))
      (node (ref "J1") (pin "AT1") (pinfunction "1_AT1") (pintype "bidirectional"))
      (node (ref "J1") (pin "AT2") (pinfunction "1_AT2") (pintype "bidirectional"))
      (node (ref "J1") (pin "BC1") (pinfunction "1_BC1") (pintype "bidirectional"))
      (node (ref "J1") (pin "BC2") (pinfunction "1_BC2") (pintype "bidirectional"))
      (node (ref "J1") (pin "BF1") (pinfunction "1_BF1") (pintype "bidirectional"))
      (node (ref "J1") (pin "BF2") (pinfunction "1_BF2") (pintype "bidirectional"))
      (node (ref "J1") (pin "BN1") (pinfunction "1_BN1") (pintype "bidirectional"))
      (node (ref "J1") (pin "BN2") (pinfunction "1_BN2") (pintype "bidirectional"))
      (node (ref "J1") (pin "BT1") (pinfunction "1_BT1") (pintype "bidirectional"))
      (node (ref "J1") (pin "BT2") (pinfunction "1_BT2") (pintype "bidirectional"))
      (node (ref "J1") (pin "CC1") (pinfunction "1_CC1") (pintype "bidirectional"))
      (node (ref "J1") (pin "CC2") (pinfunction "1_CC2") (pintype "bidirectional"))
      (node (ref "J1") (pin "CF1") (pinfunction "1_CF1") (pintype "bidirectional"))
      (node (ref "J1") (pin "CF2") (pinfunction "1_CF2") (pintype "bidirectional"))
      (node (ref "J1") (pin "CN1") (pinfunction "1_CN1") (pintype "bidirectional"))
      (node (ref "J1") (pin "CN2") (pinfunction "1_CN2") (pintype "bidirectional"))
      (node (ref "J1") (pin "CT1") (pinfunction "1_CT1") (pintype "bidirectional"))
      (node (ref "J1") (pin "CT2") (pinfunction "1_CT2") (pintype "bidirectional"))
      (node (ref "J1") (pin "DC1") (pinfunction "1_DC1") (pintype "bidirectional"))
      (node (ref "J1") (pin "DC2") (pinfunction "1_DC2") (pintype "bidirectional"))
      (node (ref "J1") (pin "DF1") (pinfunction "1_DF1") (pintype "bidirectional"))
      (node (ref "J1") (pin "DF2") (pinfunction "1_DF2") (pintype "bidirectional"))
      (node (ref "J1") (pin "DN1") (pinfunction "1_DN1") (pintype "bidirectional"))
      (node (ref "J1") (pin "DN2") (pinfunction "1_DN2") (pintype "bidirectional"))
      (node (ref "J1") (pin "DT1") (pinfunction "1_DT1") (pintype "bidirectional"))
      (node (ref "J1") (pin "DT2") (pinfunction "1_DT2") (pintype "bidirectional"))
      (node (ref "J2") (pin "4") (pinfunction "4_4") (pintype "passive"))
      (node (ref "J3") (pin "6") (pinfunction "6_6") (pintype "passive"))
      (node (ref "J4") (pin "A") (pinfunction "1_A") (pintype "bidirectional"))
      (node (ref "J4") (pin "B") (pinfunction "2_B") (pintype "bidirectional"))
      (node (ref "J4") (pin "SS") (pinfunction "37_SS") (pintype "bidirectional"))
      (node (ref "J4") (pin "TT") (pinfunction "38_TT") (pintype "bidirectional"))
      (node (ref "J4") (pin "UU") (pinfunction "39_UU") (pintype "bidirectional"))
      (node (ref "J4") (pin "VV") (pinfunction "40_VV") (pintype "bidirectional"))
      (node (ref "J5") (pin "5") (pinfunction "F_5") (pintype "passive"))
      (node (ref "R20") (pin "1") (pinfunction "1_1") (pintype "passive"))
      (node (ref "R7") (pin "1") (pinfunction "1_1") (pintype "passive"))
      (node (ref "SW2") (pin "3") (pinfunction "P_3") (pintype "passive"))
      (node (ref "SW2") (pin "4") (pinfunction "P1_4") (pintype "passive"))
      (node (ref "SW3") (pin "1") (pinfunction "1_1") (pintype "passive"))
      (node (ref "SW3") (pin "2") (pinfunction "1_2") (pintype "passive"))
      (node (ref "SW3") (pin "3") (pinfunction "1_3") (pintype "passive"))
      (node (ref "SW3") (pin "4") (pinfunction "1_4") (pintype "passive"))
      (node (ref "U1") (pin "22") (pinfunction "GND_22") (pintype "power_in"))
      (node (ref "U1") (pin "8") (pinfunction "GND_8") (pintype "power_in"))
      (node (ref "U11") (pin "1") (pinfunction "A0_1") (pintype "input"))
      (node (ref "U11") (pin "2") (pinfunction "A1_2") (pintype "input"))
      (node (ref "U11") (pin "3") (pinfunction "A2_3") (pintype "input"))
      (node (ref "U11") (pin "4") (pinfunction "GND_4") (pintype "power_in"))
      (node (ref "U11") (pin "7") (pinfunction "WP_7") (pintype "input"))
      (node (ref "U2") (pin "10") (pinfunction "VSS_10") (pintype "power_in"))
      (node (ref "U2") (pin "15") (pinfunction "A0_15") (pintype "input"))
      (node (ref "U2") (pin "16") (pinfunction "A1_16") (pintype "input"))
      (node (ref "U2") (pin "17") (pinfunction "A2_17") (pintype "input"))
    )
    (net (code "21") (name "INHIBIT") (class "Default")
      (node (ref "J1") (pin "AP2") (pinfunction "1_AP2") (pintype "bidirectional"))
    )
    (net (code "22") (name "INITIALIZE") (class "Default")
      (node (ref "J1") (pin "CR1") (pinfunction "1_CR1") (pintype "bidirectional"))
      (node (ref "Q1") (pin "1") (pinfunction "E_1") (pintype "passive"))
      (node (ref "U9") (pin "10") (pinfunction "I1_10") (pintype "input"))
      (node (ref "U9") (pin "9") (pinfunction "I0_9") (pintype "input"))
    )
    (net (code "23") (name "INT_IN_PROG") (class "Default")
      (node (ref "J1") (pin "BP2") (pinfunction "1_BP2") (pintype "bidirectional"))
    )
    (net (code "24") (name "INT_STROBE") (class "Default")
      (node (ref "J1") (pin "BD2") (pinfunction "1_BD2") (pintype "bidirectional"))
    )
    (net (code "25") (name "MEM00") (class "Default")
      (node (ref "E1") (pin "18") (pinfunction "B1_18") (pintype "bidirectional"))
      (node (ref "E4") (pin "15") (pinfunction "I/O3_15") (pintype "tri_state"))
    )
    (net (code "26") (name "MEM01") (class "Default")
      (node (ref "E1") (pin "17") (pinfunction "B2_17") (pintype "bidirectional"))
      (node (ref "E4") (pin "13") (pinfunction "I/O2_13") (pintype "tri_state"))
    )
    (net (code "27") (name "MEM02") (class "Default")
      (node (ref "E1") (pin "16") (pinfunction "B3_16") (pintype "bidirectional"))
      (node (ref "E4") (pin "12") (pinfunction "I/O1_12") (pintype "tri_state"))
    )
    (net (code "28") (name "MEM03") (class "Default")
      (node (ref "E1") (pin "15") (pinfunction "B4_15") (pintype "bidirectional"))
      (node (ref "E4") (pin "11") (pinfunction "I/O0_11") (pintype "tri_state"))
    )
    (net (code "29") (name "MEM04") (class "Default")
      (node (ref "E2") (pin "18") (pinfunction "B1_18") (pintype "bidirectional"))
      (node (ref "E3") (pin "16") (pinfunction "I/O4_16") (pintype "tri_state"))
    )
    (net (code "30") (name "MEM05") (class "Default")
      (node (ref "E2") (pin "17") (pinfunction "B2_17") (pintype "bidirectional"))
      (node (ref "E3") (pin "17") (pinfunction "I/O5_17") (pintype "tri_state"))
    )
    (net (code "31") (name "MEM06") (class "Default")
      (node (ref "E2") (pin "16") (pinfunction "B3_16") (pintype "bidirectional"))
      (node (ref "E3") (pin "18") (pinfunction "I/O6_18") (pintype "tri_state"))
    )
    (net (code "32") (name "MEM07") (class "Default")
      (node (ref "E2") (pin "15") (pinfunction "B4_15") (pintype "bidirectional"))
      (node (ref "E3") (pin "19") (pinfunction "I/O7_19") (pintype "tri_state"))
    )
    (net (code "33") (name "MEM08") (class "Default")
      (node (ref "E2") (pin "14") (pinfunction "B5_14") (pintype "bidirectional"))
      (node (ref "E3") (pin "15") (pinfunction "I/O3_15") (pintype "tri_state"))
    )
    (net (code "34") (name "MEM09") (class "Default")
      (node (ref "E2") (pin "13") (pinfunction "B6_13") (pintype "bidirectional"))
      (node (ref "E3") (pin "13") (pinfunction "I/O2_13") (pintype "tri_state"))
    )
    (net (code "35") (name "MEM10") (class "Default")
      (node (ref "E2") (pin "12") (pinfunction "B7_12") (pintype "bidirectional"))
      (node (ref "E3") (pin "12") (pinfunction "I/O1_12") (pintype "tri_state"))
    )
    (net (code "36") (name "MEM11") (class "Default")
      (node (ref "E2") (pin "11") (pinfunction "B8_11") (pintype "bidirectional"))
      (node (ref "E3") (pin "11") (pinfunction "I/O0_11") (pintype "tri_state"))
    )
    (net (code "37") (name "Net-(B1-+-Pad+@1)") (class "Default")
      (node (ref "B1") (pin "+") (pinfunction "+_+") (pintype "passive"))
      (node (ref "B1") (pin "+@1") (pinfunction "+_+@1") (pintype "passive"))
      (node (ref "B1") (pin "+@2") (pinfunction "+_+@2") (pintype "passive"))
      (node (ref "B1") (pin "+@3") (pinfunction "+_+@3") (pintype "passive"))
      (node (ref "B1") (pin "+@4") (pinfunction "+_+@4") (pintype "passive"))
      (node (ref "D2") (pin "A") (pinfunction "A_A") (pintype "passive"))
    )
    (net (code "38") (name "Net-(E1A-A5)") (class "Default")
      (node (ref "E1") (pin "6") (pinfunction "A5_6") (pintype "bidirectional"))
      (node (ref "R25") (pin "2") (pinfunction "2_2") (pintype "passive"))
    )
    (net (code "39") (name "Net-(E1A-A6)") (class "Default")
      (node (ref "E1") (pin "7") (pinfunction "A6_7") (pintype "bidirectional"))
      (node (ref "R25") (pin "3") (pinfunction "3_3") (pintype "passive"))
    )
    (net (code "40") (name "Net-(E1A-A7)") (class "Default")
      (node (ref "E1") (pin "8") (pinfunction "A7_8") (pintype "bidirectional"))
      (node (ref "R25") (pin "4") (pinfunction "4_4") (pintype "passive"))
    )
    (net (code "41") (name "Net-(E1A-A8)") (class "Default")
      (node (ref "E1") (pin "9") (pinfunction "A8_9") (pintype "bidirectional"))
      (node (ref "R25") (pin "5") (pinfunction "5_5") (pintype "passive"))
    )
    (net (code "42") (name "Net-(E5A-Y0)") (class "Default")
      (node (ref "E5") (pin "15") (pinfunction "Y0_15") (pintype "output"))
      (node (ref "S1") (pin "1") (pinfunction "1_1") (pintype "passive"))
    )
    (net (code "43") (name "Net-(E5A-Y1)") (class "Default")
      (node (ref "E5") (pin "14") (pinfunction "Y1_14") (pintype "output"))
      (node (ref "S1") (pin "2") (pinfunction "2_2") (pintype "passive"))
    )
    (net (code "44") (name "Net-(E5A-Y2)") (class "Default")
      (node (ref "E5") (pin "13") (pinfunction "Y2_13") (pintype "output"))
      (node (ref "S1") (pin "3") (pinfunction "3_3") (pintype "passive"))
    )
    (net (code "45") (name "Net-(E5A-Y3)") (class "Default")
      (node (ref "E5") (pin "12") (pinfunction "Y3_12") (pintype "output"))
      (node (ref "S1") (pin "4") (pinfunction "4_4") (pintype "passive"))
    )
    (net (code "46") (name "Net-(E5A-Y4)") (class "Default")
      (node (ref "E5") (pin "11") (pinfunction "Y4_11") (pintype "output"))
      (node (ref "S1") (pin "5") (pinfunction "5_5") (pintype "passive"))
    )
    (net (code "47") (name "Net-(E5A-Y5)") (class "Default")
      (node (ref "E5") (pin "10") (pinfunction "Y5_10") (pintype "output"))
      (node (ref "S1") (pin "6") (pinfunction "6_6") (pintype "passive"))
    )
    (net (code "48") (name "Net-(E5A-Y6)") (class "Default")
      (node (ref "E5") (pin "9") (pinfunction "Y6_9") (pintype "output"))
      (node (ref "S1") (pin "7") (pinfunction "7_7") (pintype "passive"))
    )
    (net (code "49") (name "Net-(E5A-Y7)") (class "Default")
      (node (ref "E5") (pin "7") (pinfunction "Y7_7") (pintype "output"))
      (node (ref "S1") (pin "8") (pinfunction "8_8") (pintype "passive"))
    )
    (net (code "50") (name "Net-(E6A-I0)") (class "Default")
      (node (ref "E6") (pin "1") (pinfunction "I0_1") (pintype "input"))
      (node (ref "R23") (pin "3") (pinfunction "1_3") (pintype "passive"))
      (node (ref "S1") (pin "14") (pinfunction "14_14") (pintype "passive"))
    )
    (net (code "51") (name "Net-(E6A-I1)") (class "Default")
      (node (ref "E6") (pin "2") (pinfunction "I1_2") (pintype "input"))
      (node (ref "R23") (pin "4") (pinfunction "1_4") (pintype "passive"))
      (node (ref "S1") (pin "13") (pinfunction "13_13") (pintype "passive"))
    )
    (net (code "52") (name "Net-(E6A-I2)") (class "Default")
      (node (ref "E6") (pin "3") (pinfunction "I2_3") (pintype "input"))
      (node (ref "R23") (pin "5") (pinfunction "1_5") (pintype "passive"))
      (node (ref "S1") (pin "12") (pinfunction "12_12") (pintype "passive"))
    )
    (net (code "53") (name "Net-(E6A-I3)") (class "Default")
      (node (ref "E6") (pin "4") (pinfunction "I3_4") (pintype "input"))
      (node (ref "R23") (pin "6") (pinfunction "1_6") (pintype "passive"))
      (node (ref "S1") (pin "11") (pinfunction "11_11") (pintype "passive"))
    )
    (net (code "54") (name "Net-(E6A-I4)") (class "Default")
      (node (ref "E6") (pin "5") (pinfunction "I4_5") (pintype "input"))
      (node (ref "R23") (pin "7") (pinfunction "1_7") (pintype "passive"))
      (node (ref "S1") (pin "10") (pinfunction "10_10") (pintype "passive"))
    )
    (net (code "55") (name "Net-(E6A-I5)") (class "Default")
      (node (ref "E6") (pin "6") (pinfunction "I5_6") (pintype "input"))
      (node (ref "R23") (pin "8") (pinfunction "1_8") (pintype "passive"))
      (node (ref "S1") (pin "9") (pinfunction "9_9") (pintype "passive"))
    )
    (net (code "56") (name "Net-(E6A-I6)") (class "Default")
      (node (ref "E6") (pin "11") (pinfunction "I6_11") (pintype "input"))
      (node (ref "R23") (pin "2") (pinfunction "1_2") (pintype "passive"))
      (node (ref "S1") (pin "15") (pinfunction "15_15") (pintype "passive"))
    )
    (net (code "57") (name "Net-(E6A-I7)") (class "Default")
      (node (ref "E6") (pin "12") (pinfunction "I7_12") (pintype "input"))
      (node (ref "R23") (pin "1") (pinfunction "1_1") (pintype "passive"))
      (node (ref "S1") (pin "16") (pinfunction "16_16") (pintype "passive"))
    )
    (net (code "58") (name "Net-(Q1-B)") (class "Default")
      (node (ref "Q1") (pin "2") (pinfunction "B_2") (pintype "passive"))
      (node (ref "R10") (pin "2") (pinfunction "2_2") (pintype "passive"))
    )
    (net (code "59") (name "Net-(Q1-C)") (class "Default")
      (node (ref "Q1") (pin "3") (pinfunction "C_3") (pintype "passive"))
      (node (ref "R5") (pin "1") (pinfunction "1_1") (pintype "passive"))
    )
    (net (code "60") (name "Net-(Q2-B)") (class "Default")
      (node (ref "Q2") (pin "2") (pinfunction "B_2") (pintype "passive"))
      (node (ref "R11") (pin "2") (pinfunction "2_2") (pintype "passive"))
    )
    (net (code "61") (name "Net-(Q2-C)") (class "Default")
      (node (ref "Q2") (pin "3") (pinfunction "C_3") (pintype "passive"))
      (node (ref "R6") (pin "1") (pinfunction "1_1") (pintype "passive"))
    )
    (net (code "62") (name "Net-(Q3-B)") (class "Default")
      (node (ref "Q3") (pin "2") (pinfunction "B_2") (pintype "passive"))
      (node (ref "R24") (pin "2") (pinfunction "2_2") (pintype "passive"))
    )
    (net (code "63") (name "Net-(SW2-S)") (class "Default")
      (node (ref "R12") (pin "2") (pinfunction "2_2") (pintype "passive"))
      (node (ref "SW2") (pin "1") (pinfunction "S_1") (pintype "passive"))
      (node (ref "SW2") (pin "2") (pinfunction "S1_2") (pintype "passive"))
    )
    (net (code "64") (name "Net-(SW3A-2)") (class "Default")
      (node (ref "R9") (pin "2") (pinfunction "2_2") (pintype "passive"))
      (node (ref "SW3") (pin "8") (pinfunction "2_8") (pintype "passive"))
    )
    (net (code "65") (name "Net-(SW3B-2)") (class "Default")
      (node (ref "R8") (pin "2") (pinfunction "2_2") (pintype "passive"))
      (node (ref "SW3") (pin "7") (pinfunction "2_7") (pintype "passive"))
    )
    (net (code "66") (name "Net-(SW3C-2)") (class "Default")
      (node (ref "R4") (pin "2") (pinfunction "2_2") (pintype "passive"))
      (node (ref "SW3") (pin "6") (pinfunction "2_6") (pintype "passive"))
    )
    (net (code "67") (name "Net-(SW3D-2)") (class "Default")
      (node (ref "R3") (pin "2") (pinfunction "2_2") (pintype "passive"))
      (node (ref "SW3") (pin "5") (pinfunction "2_5") (pintype "passive"))
    )
    (net (code "68") (name "Net-(U1-PB6(XTAL1{slash}TOSC1))") (class "Default")
      (node (ref "C9") (pin "1") (pinfunction "1_1") (pintype "passive"))
      (node (ref "R18") (pin "1") (pinfunction "1_1") (pintype "passive"))
      (node (ref "U1") (pin "9") (pinfunction "PB6(XTAL1/TOSC1)_9") (pintype "bidirectional"))
      (node (ref "Y1") (pin "2") (pinfunction "2_2") (pintype "passive"))
    )
    (net (code "69") (name "Net-(U1-PB7(XTAL2{slash}TOSC2))") (class "Default")
      (node (ref "C7") (pin "1") (pinfunction "1_1") (pintype "passive"))
      (node (ref "R18") (pin "2") (pinfunction "2_2") (pintype "passive"))
      (node (ref "U1") (pin "10") (pinfunction "PB7(XTAL2/TOSC2)_10") (pintype "bidirectional"))
      (node (ref "Y1") (pin "1") (pinfunction "1_1") (pintype "passive"))
    )
    (net (code "70") (name "Net-(U1-PD0(RXD))") (class "Default")
      (node (ref "R16") (pin "1") (pinfunction "1_1") (pintype "passive"))
      (node (ref "U1") (pin "2") (pinfunction "PD0(RXD)_2") (pintype "bidirectional"))
    )
    (net (code "71") (name "Net-(U1-PD1(TXD))") (class "Default")
      (node (ref "R17") (pin "1") (pinfunction "1_1") (pintype "passive"))
      (node (ref "U1") (pin "3") (pinfunction "PD1(TXD)_3") (pintype "bidirectional"))
    )
    (net (code "72") (name "Net-(U8A-O)") (class "Default")
      (node (ref "U8") (pin "12") (pinfunction "O_12") (pintype "output"))
      (node (ref "U8") (pin "3") (pinfunction "I0_3") (pintype "input"))
      (node (ref "U8") (pin "4") (pinfunction "I1_4") (pintype "input"))
      (node (ref "U8") (pin "5") (pinfunction "I2_5") (pintype "input"))
    )
    (net (code "73") (name "Net-(U8C-I0)") (class "Default")
      (node (ref "U8") (pin "9") (pinfunction "I0_9") (pintype "input"))
      (node (ref "U9") (pin "8") (pinfunction "O_8") (pintype "output"))
    )
    (net (code "74") (name "Net-(U8C-I1)") (class "Default")
      (node (ref "U8") (pin "10") (pinfunction "I1_10") (pintype "input"))
      (node (ref "U9") (pin "6") (pinfunction "O_6") (pintype "output"))
    )
    (net (code "75") (name "Net-(U8C-O)") (class "Default")
      (node (ref "U8") (pin "8") (pinfunction "O_8") (pintype "output"))
      (node (ref "U9") (pin "13") (pinfunction "I1_13") (pintype "input"))
      (node (ref "U9") (pin "2") (pinfunction "I1_2") (pintype "input"))
    )
    (net (code "76") (name "Net-(U9A-O)") (class "Default")
      (node (ref "U9") (pin "12") (pinfunction "I0_12") (pintype "input"))
      (node (ref "U9") (pin "3") (pinfunction "O_3") (pintype "output"))
    )
    (net (code "77") (name "Net-(U10A-C1+)") (class "Default")
      (node (ref "C14") (pin "1") (pinfunction "1_1") (pintype "passive"))
      (node (ref "U10") (pin "1") (pinfunction "C1+_1") (pintype "bidirectional"))
    )
    (net (code "78") (name "Net-(U10A-C1-)") (class "Default")
      (node (ref "C14") (pin "2") (pinfunction "2_2") (pintype "passive"))
      (node (ref "U10") (pin "3") (pinfunction "C1-_3") (pintype "bidirectional"))
    )
    (net (code "79") (name "Net-(U10A-C2+)") (class "Default")
      (node (ref "C15") (pin "1") (pinfunction "1_1") (pintype "passive"))
      (node (ref "U10") (pin "4") (pinfunction "C2+_4") (pintype "bidirectional"))
    )
    (net (code "80") (name "Net-(U10A-C2-)") (class "Default")
      (node (ref "C15") (pin "2") (pinfunction "2_2") (pintype "passive"))
      (node (ref "U10") (pin "5") (pinfunction "C2-_5") (pintype "bidirectional"))
    )
    (net (code "81") (name "Net-(U10A-V+)") (class "Default")
      (node (ref "C16") (pin "1") (pinfunction "1_1") (pintype "passive"))
      (node (ref "U10") (pin "2") (pinfunction "V+_2") (pintype "bidirectional"))
    )
    (net (code "82") (name "Net-(U10A-V-)") (class "Default")
      (node (ref "C17") (pin "2") (pinfunction "2_2") (pintype "passive"))
      (node (ref "U10") (pin "6") (pinfunction "V-_6") (pintype "bidirectional"))
    )
    (net (code "83") (name "POWER_OK") (class "Default")
      (node (ref "J1") (pin "BV2") (pinfunction "1_BV2") (pintype "bidirectional"))
      (node (ref "R24") (pin "1") (pinfunction "1_1") (pintype "passive"))
    )
    (net (code "84") (name "PROG") (class "Default")
      (node (ref "C11") (pin "2") (pinfunction "2_2") (pintype "passive"))
      (node (ref "J2") (pin "1") (pinfunction "1_1") (pintype "passive"))
      (node (ref "R20") (pin "2") (pinfunction "2_2") (pintype "passive"))
      (node (ref "U10") (pin "11") (pinfunction "T1IN_11") (pintype "input"))
      (node (ref "U10") (pin "12") (pinfunction "R1OUT_12") (pintype "output"))
    )
    (net (code "85") (name "PULSE_LA") (class "Default")
      (node (ref "J1") (pin "DR2") (pinfunction "1_DR2") (pintype "bidirectional"))
      (node (ref "Q2") (pin "1") (pinfunction "E_1") (pintype "passive"))
    )
    (net (code "86") (name "RETURN") (class "Default")
      (node (ref "J1") (pin "AR2") (pinfunction "1_AR2") (pintype "bidirectional"))
    )
    (net (code "87") (name "RXD") (class "Default")
      (node (ref "J2") (pin "2") (pinfunction "2_2") (pintype "passive"))
      (node (ref "R16") (pin "2") (pinfunction "2_2") (pintype "passive"))
      (node (ref "U10") (pin "9") (pinfunction "R2OUT_9") (pintype "output"))
    )
    (net (code "88") (name "RXD232") (class "Default")
      (node (ref "J4") (pin "J") (pinfunction "8_J") (pintype "bidirectional"))
      (node (ref "J5") (pin "2") (pinfunction "F_2") (pintype "passive"))
      (node (ref "U10") (pin "8") (pinfunction "R2IN_8") (pintype "input"))
    )
    (net (code "89") (name "R_RUN") (class "Default")
      (node (ref "R2") (pin "1") (pinfunction "1_1") (pintype "passive"))
      (node (ref "U1") (pin "14") (pinfunction "PB0(ICP)_14") (pintype "bidirectional"))
    )
    (net (code "90") (name "R_SW") (class "Default")
      (node (ref "C10") (pin "1") (pinfunction "1_1") (pintype "passive"))
      (node (ref "R1") (pin "1") (pinfunction "1_1") (pintype "passive"))
      (node (ref "R12") (pin "1") (pinfunction "1_1") (pintype "passive"))
      (node (ref "U1") (pin "15") (pinfunction "PB1(OC1A)_15") (pintype "bidirectional"))
    )
    (net (code "91") (name "SCL") (class "Default")
      (node (ref "R22") (pin "1") (pinfunction "1_1") (pintype "passive"))
      (node (ref "U1") (pin "28") (pinfunction "PC5(ADC5/SCL)_28") (pintype "bidirectional"))
      (node (ref "U11") (pin "6") (pinfunction "SCL_6") (pintype "input"))
      (node (ref "U2") (pin "12") (pinfunction "SCL_12") (pintype "input"))
    )
    (net (code "92") (name "SDA") (class "Default")
      (node (ref "R21") (pin "1") (pinfunction "1_1") (pintype "passive"))
      (node (ref "U1") (pin "27") (pinfunction "PC4(ADC4/SDA)_27") (pintype "bidirectional"))
      (node (ref "U11") (pin "5") (pinfunction "SDA_5") (pintype "bidirectional"))
      (node (ref "U2") (pin "13") (pinfunction "SDA_13") (pintype "bidirectional"))
    )
    (net (code "93") (name "SET_FF") (class "Default")
      (node (ref "U1") (pin "4") (pinfunction "PD2(INT0)_4") (pintype "bidirectional"))
      (node (ref "U9") (pin "1") (pinfunction "I0_1") (pintype "input"))
    )
    (net (code "94") (name "SHOW_DATA") (class "Default")
      (node (ref "U1") (pin "5") (pinfunction "PD3(INT1)_5") (pintype "bidirectional"))
      (node (ref "U8") (pin "1") (pinfunction "I0_1") (pintype "input"))
    )
    (net (code "95") (name "SOURCE") (class "Default")
      (node (ref "E8") (pin "6") (pinfunction "A5_6") (pintype "input"))
      (node (ref "J1") (pin "AL2") (pinfunction "1_AL2") (pintype "bidirectional"))
    )
    (net (code "96") (name "STROBE") (class "Default")
      (node (ref "J1") (pin "AM2") (pinfunction "1_AM2") (pintype "bidirectional"))
    )
    (net (code "97") (name "SW") (class "Default")
      (node (ref "J1") (pin "DV2") (pinfunction "1_DV2") (pintype "bidirectional"))
      (node (ref "R1") (pin "2") (pinfunction "2_2") (pintype "passive"))
    )
    (net (code "98") (name "TP1") (class "Default")
      (node (ref "J1") (pin "CD2") (pinfunction "1_CD2") (pintype "bidirectional"))
    )
    (net (code "99") (name "TP2") (class "Default")
      (node (ref "J1") (pin "CE2") (pinfunction "1_CE2") (pintype "bidirectional"))
    )
    (net (code "100") (name "TP3") (class "Default")
      (node (ref "J1") (pin "CH2") (pinfunction "1_CH2") (pintype "bidirectional"))
    )
    (net (code "101") (name "TP4") (class "Default")
      (node (ref "J1") (pin "CJ2") (pinfunction "1_CJ2") (pintype "bidirectional"))
      (node (ref "U9") (pin "4") (pinfunction "I0_4") (pintype "input"))
      (node (ref "U9") (pin "5") (pinfunction "I1_5") (pintype "input"))
    )
    (net (code "102") (name "TXD") (class "Default")
      (node (ref "J2") (pin "3") (pinfunction "3_3") (pintype "passive"))
      (node (ref "R17") (pin "2") (pinfunction "2_2") (pintype "passive"))
      (node (ref "U10") (pin "10") (pinfunction "T2IN_10") (pintype "input"))
    )
    (net (code "103") (name "TXD232") (class "Default")
      (node (ref "J4") (pin "F") (pinfunction "6_F") (pintype "bidirectional"))
      (node (ref "J5") (pin "3") (pinfunction "F_3") (pintype "passive"))
      (node (ref "U10") (pin "7") (pinfunction "T2OUT_7") (pintype "output"))
    )
    (net (code "104") (name "V+") (class "Default")
      (node (ref "C20") (pin "1") (pinfunction "1_1") (pintype "passive"))
      (node (ref "C21") (pin "1") (pinfunction "1_1") (pintype "passive"))
      (node (ref "D2") (pin "C") (pinfunction "C_C") (pintype "passive"))
      (node (ref "D3") (pin "C") (pinfunction "C_C") (pintype "passive"))
      (node (ref "E3") (pin "28") (pinfunction "VCC_28") (pintype "power_in"))
      (node (ref "E4") (pin "28") (pinfunction "VCC_28") (pintype "power_in"))
      (node (ref "R15") (pin "2") (pinfunction "2_2") (pintype "passive"))
    )
    (net (code "105") (name "VCC") (class "Default")
      (node (ref "C1") (pin "1") (pinfunction "1_1") (pintype "passive"))
      (node (ref "C12") (pin "1") (pinfunction "1_1") (pintype "passive"))
      (node (ref "C13") (pin "1") (pinfunction "1_1") (pintype "passive"))
      (node (ref "C16") (pin "2") (pinfunction "2_2") (pintype "passive"))
      (node (ref "C18") (pin "1") (pinfunction "1_1") (pintype "passive"))
      (node (ref "C19") (pin "1") (pinfunction "1_1") (pintype "passive"))
      (node (ref "C2") (pin "1") (pinfunction "1_1") (pintype "passive"))
      (node (ref "C23") (pin "1") (pinfunction "1_1") (pintype "passive"))
      (node (ref "C24") (pin "1") (pinfunction "1_1") (pintype "passive"))
      (node (ref "C25") (pin "1") (pinfunction "1_1") (pintype "passive"))
      (node (ref "C26") (pin "1") (pinfunction "1_1") (pintype "passive"))
      (node (ref "C27") (pin "1") (pinfunction "1_1") (pintype "passive"))
      (node (ref "C28") (pin "1") (pinfunction "1_1") (pintype "passive"))
      (node (ref "C29") (pin "1") (pinfunction "1_1") (pintype "passive"))
      (node (ref "C3") (pin "1") (pinfunction "1_1") (pintype "passive"))
      (node (ref "C30") (pin "+") (pinfunction "+_+") (pintype "passive"))
      (node (ref "C4") (pin "1") (pinfunction "1_1") (pintype "passive"))
      (node (ref "C5") (pin "1") (pinfunction "1_1") (pintype "passive"))
      (node (ref "C6") (pin "1") (pinfunction "1_1") (pintype "passive"))
      (node (ref "C8") (pin "1") (pinfunction "1_1") (pintype "passive"))
      (node (ref "D1") (pin "C") (pinfunction "C_C") (pintype "passive"))
      (node (ref "D3") (pin "A") (pinfunction "A_A") (pintype "passive"))
      (node (ref "J1") (pin "AA2") (pinfunction "1_AA2") (pintype "bidirectional"))
      (node (ref "J1") (pin "BA2") (pinfunction "1_BA2") (pintype "bidirectional"))
      (node (ref "J1") (pin "CA2") (pinfunction "1_CA2") (pintype "bidirectional"))
      (node (ref "J3") (pin "2") (pinfunction "2_2") (pintype "passive"))
      (node (ref "R13") (pin "2") (pinfunction "2_2") (pintype "passive"))
      (node (ref "R14") (pin "2") (pinfunction "2_2") (pintype "passive"))
      (node (ref "R19") (pin "2") (pinfunction "2_2") (pintype "passive"))
      (node (ref "R21") (pin "2") (pinfunction "2_2") (pintype "passive"))
      (node (ref "R22") (pin "2") (pinfunction "2_2") (pintype "passive"))
      (node (ref "R23") (pin "10") (pinfunction "2_10") (pintype "passive"))
      (node (ref "R23") (pin "11") (pinfunction "2_11") (pintype "passive"))
      (node (ref "R23") (pin "12") (pinfunction "2_12") (pintype "passive"))
      (node (ref "R23") (pin "13") (pinfunction "2_13") (pintype "passive"))
      (node (ref "R23") (pin "14") (pinfunction "2_14") (pintype "passive"))
      (node (ref "R23") (pin "15") (pinfunction "2_15") (pintype "passive"))
      (node (ref "R23") (pin "16") (pinfunction "2_16") (pintype "passive"))
      (node (ref "R23") (pin "9") (pinfunction "2_9") (pintype "passive"))
      (node (ref "R25") (pin "1") (pinfunction "1_1") (pintype "passive"))
      (node (ref "R5") (pin "2") (pinfunction "2_2") (pintype "passive"))
      (node (ref "R6") (pin "2") (pinfunction "2_2") (pintype "passive"))
      (node (ref "U1") (pin "20") (pinfunction "AVCC_20") (pintype "power_in"))
      (node (ref "U1") (pin "21") (pinfunction "AREF_21") (pintype "passive"))
      (node (ref "U1") (pin "7") (pinfunction "VCC_7") (pintype "power_in"))
      (node (ref "U11") (pin "8") (pinfunction "VCC_8") (pintype "power_in"))
      (node (ref "U2") (pin "18") (pinfunction "~{RESET}_18") (pintype "input"))
      (node (ref "U2") (pin "9") (pinfunction "VDD_9") (pintype "power_in"))
      (node (ref "U7") (pin "12") (pinfunction "I0_12") (pintype "input"))
      (node (ref "U7") (pin "13") (pinfunction "I1_13") (pintype "input"))
    )
    (net (code "106") (name "WRITE") (class "Default")
      (node (ref "E8") (pin "4") (pinfunction "A3_4") (pintype "input"))
      (node (ref "J1") (pin "AS2") (pinfunction "1_AS2") (pintype "bidirectional"))
    )
    (net (code "107") (name "W_DATA_00") (class "Default")
      (node (ref "U2") (pin "7") (pinfunction "GPB6_7") (pintype "bidirectional"))
      (node (ref "U3") (pin "1") (pinfunction "I0_1") (pintype "input"))
    )
    (net (code "108") (name "W_DATA_01") (class "Default")
      (node (ref "U2") (pin "6") (pinfunction "GPB5_6") (pintype "bidirectional"))
      (node (ref "U3") (pin "4") (pinfunction "I0_4") (pintype "input"))
    )
    (net (code "109") (name "W_DATA_02") (class "Default")
      (node (ref "U2") (pin "5") (pinfunction "GPB4_5") (pintype "bidirectional"))
      (node (ref "U3") (pin "12") (pinfunction "I0_12") (pintype "input"))
    )
    (net (code "110") (name "W_DATA_03") (class "Default")
      (node (ref "U2") (pin "3") (pinfunction "GPB2_3") (pintype "bidirectional"))
      (node (ref "U3") (pin "9") (pinfunction "I0_9") (pintype "input"))
    )
    (net (code "111") (name "W_DATA_04") (class "Default")
      (node (ref "U2") (pin "2") (pinfunction "GPB1_2") (pintype "bidirectional"))
      (node (ref "U4") (pin "1") (pinfunction "I0_1") (pintype "input"))
    )
    (net (code "112") (name "W_DATA_05") (class "Default")
      (node (ref "U2") (pin "1") (pinfunction "GPB0_1") (pintype "bidirectional"))
      (node (ref "U4") (pin "4") (pinfunction "I0_4") (pintype "input"))
    )
    (net (code "113") (name "W_DATA_06") (class "Default")
      (node (ref "U2") (pin "27") (pinfunction "GPA6_27") (pintype "bidirectional"))
      (node (ref "U4") (pin "12") (pinfunction "I0_12") (pintype "input"))
    )
    (net (code "114") (name "W_DATA_07") (class "Default")
      (node (ref "U2") (pin "26") (pinfunction "GPA5_26") (pintype "bidirectional"))
      (node (ref "U4") (pin "9") (pinfunction "I0_9") (pintype "input"))
    )
    (net (code "115") (name "W_DATA_08") (class "Default")
      (node (ref "U2") (pin "25") (pinfunction "GPA4_25") (pintype "bidirectional"))
      (node (ref "U5") (pin "1") (pinfunction "I0_1") (pintype "input"))
    )
    (net (code "116") (name "W_DATA_09") (class "Default")
      (node (ref "U2") (pin "23") (pinfunction "GPA2_23") (pintype "bidirectional"))
      (node (ref "U5") (pin "4") (pinfunction "I0_4") (pintype "input"))
    )
    (net (code "117") (name "W_DATA_10") (class "Default")
      (node (ref "U2") (pin "22") (pinfunction "GPA1_22") (pintype "bidirectional"))
      (node (ref "U5") (pin "12") (pinfunction "I0_12") (pintype "input"))
    )
    (net (code "118") (name "W_DATA_11") (class "Default")
      (node (ref "U2") (pin "21") (pinfunction "GPA0_21") (pintype "bidirectional"))
      (node (ref "U5") (pin "9") (pinfunction "I0_9") (pintype "input"))
    )
    (net (code "119") (name "W_INITIALIZE") (class "Default")
      (node (ref "R10") (pin "1") (pinfunction "1_1") (pintype "passive"))
      (node (ref "R13") (pin "1") (pinfunction "1_1") (pintype "passive"))
      (node (ref "U1") (pin "23") (pinfunction "PC0(ADC0)_23") (pintype "bidirectional"))
    )
    (net (code "120") (name "W_PULSE_LA") (class "Default")
      (node (ref "R11") (pin "1") (pinfunction "1_1") (pintype "passive"))
      (node (ref "R14") (pin "1") (pinfunction "1_1") (pintype "passive"))
      (node (ref "U1") (pin "24") (pinfunction "PC1(ADC1)_24") (pintype "bidirectional"))
    )
    (net (code "121") (name "W_STOP") (class "Default")
      (node (ref "U1") (pin "26") (pinfunction "PC3(ADC3)_26") (pintype "bidirectional"))
      (node (ref "U7") (pin "10") (pinfunction "I1_10") (pintype "input"))
      (node (ref "U7") (pin "9") (pinfunction "I0_9") (pintype "input"))
    )
    (net (code "122") (name "unconnected-(E8A-Y8-Pad11)") (class "Default")
      (node (ref "E8") (pin "11") (pinfunction "Y8_11") (pintype "tri_state"))
    )
    (net (code "123") (name "unconnected-(J1A-1-PadAA1)") (class "Default")
      (node (ref "J1") (pin "AA1") (pinfunction "1_AA1") (pintype "bidirectional"))
    )
    (net (code "124") (name "unconnected-(J1AK-1-PadBA1)") (class "Default")
      (node (ref "J1") (pin "BA1") (pinfunction "1_BA1") (pintype "bidirectional"))
    )
    (net (code "125") (name "unconnected-(J1AM-1-PadBB1)") (class "Default")
      (node (ref "J1") (pin "BB1") (pinfunction "1_BB1") (pintype "bidirectional"))
    )
    (net (code "126") (name "unconnected-(J1BN-1-PadBS2)") (class "Default")
      (node (ref "J1") (pin "BS2") (pinfunction "1_BS2") (pintype "bidirectional"))
    )
    (net (code "127") (name "unconnected-(J1BU-1-PadCA1)") (class "Default")
      (node (ref "J1") (pin "CA1") (pinfunction "1_CA1") (pintype "bidirectional"))
    )
    (net (code "128") (name "unconnected-(J1BW-1-PadCB1)") (class "Default")
      (node (ref "J1") (pin "CB1") (pinfunction "1_CB1") (pintype "bidirectional"))
    )
    (net (code "129") (name "unconnected-(J1C-1-PadAB1)") (class "Default")
      (node (ref "J1") (pin "AB1") (pinfunction "1_AB1") (pintype "bidirectional"))
    )
    (net (code "130") (name "unconnected-(J1DE-1-PadDA1)") (class "Default")
      (node (ref "J1") (pin "DA1") (pinfunction "1_DA1") (pintype "bidirectional"))
    )
    (net (code "131") (name "unconnected-(J1DG-1-PadDB1)") (class "Default")
      (node (ref "J1") (pin "DB1") (pinfunction "1_DB1") (pintype "bidirectional"))
    )
    (net (code "132") (name "unconnected-(J4-3-PadC)") (class "Default")
      (node (ref "J4") (pin "C") (pinfunction "3_C") (pintype "bidirectional"))
    )
    (net (code "133") (name "unconnected-(J4-4-PadD)") (class "Default")
      (node (ref "J4") (pin "D") (pinfunction "4_D") (pintype "bidirectional"))
    )
    (net (code "134") (name "unconnected-(J4-5-PadE)") (class "Default")
      (node (ref "J4") (pin "E") (pinfunction "5_E") (pintype "bidirectional"))
    )
    (net (code "135") (name "unconnected-(J4-7-PadH)") (class "Default")
      (node (ref "J4") (pin "H") (pinfunction "7_H") (pintype "bidirectional"))
    )
    (net (code "136") (name "unconnected-(J4-9-PadK)") (class "Default")
      (node (ref "J4") (pin "K") (pinfunction "9_K") (pintype "bidirectional"))
    )
    (net (code "137") (name "unconnected-(J4-10-PadL)") (class "Default")
      (node (ref "J4") (pin "L") (pinfunction "10_L") (pintype "bidirectional"))
    )
    (net (code "138") (name "unconnected-(J4-11-PadM)") (class "Default")
      (node (ref "J4") (pin "M") (pinfunction "11_M") (pintype "bidirectional"))
    )
    (net (code "139") (name "unconnected-(J4-12-PadN)") (class "Default")
      (node (ref "J4") (pin "N") (pinfunction "12_N") (pintype "bidirectional"))
    )
    (net (code "140") (name "unconnected-(J4-13-PadP)") (class "Default")
      (node (ref "J4") (pin "P") (pinfunction "13_P") (pintype "bidirectional"))
    )
    (net (code "141") (name "unconnected-(J4-14-PadR)") (class "Default")
      (node (ref "J4") (pin "R") (pinfunction "14_R") (pintype "bidirectional"))
    )
    (net (code "142") (name "unconnected-(J4-15-PadS)") (class "Default")
      (node (ref "J4") (pin "S") (pinfunction "15_S") (pintype "bidirectional"))
    )
    (net (code "143") (name "unconnected-(J4-16-PadT)") (class "Default")
      (node (ref "J4") (pin "T") (pinfunction "16_T") (pintype "bidirectional"))
    )
    (net (code "144") (name "unconnected-(J4-17-PadU)") (class "Default")
      (node (ref "J4") (pin "U") (pinfunction "17_U") (pintype "bidirectional"))
    )
    (net (code "145") (name "unconnected-(J4-18-PadV)") (class "Default")
      (node (ref "J4") (pin "V") (pinfunction "18_V") (pintype "bidirectional"))
    )
    (net (code "146") (name "unconnected-(J4-19-PadW)") (class "Default")
      (node (ref "J4") (pin "W") (pinfunction "19_W") (pintype "bidirectional"))
    )
    (net (code "147") (name "unconnected-(J4-20-PadX)") (class "Default")
      (node (ref "J4") (pin "X") (pinfunction "20_X") (pintype "bidirectional"))
    )
    (net (code "148") (name "unconnected-(J4-21-PadY)") (class "Default")
      (node (ref "J4") (pin "Y") (pinfunction "21_Y") (pintype "bidirectional"))
    )
    (net (code "149") (name "unconnected-(J4-23-PadAA)") (class "Default")
      (node (ref "J4") (pin "AA") (pinfunction "23_AA") (pintype "bidirectional"))
    )
    (net (code "150") (name "unconnected-(J4-24-PadBB)") (class "Default")
      (node (ref "J4") (pin "BB") (pinfunction "24_BB") (pintype "bidirectional"))
    )
    (net (code "151") (name "unconnected-(J4-25-PadCC)") (class "Default")
      (node (ref "J4") (pin "CC") (pinfunction "25_CC") (pintype "bidirectional"))
    )
    (net (code "152") (name "unconnected-(J4-26-PadDD)") (class "Default")
      (node (ref "J4") (pin "DD") (pinfunction "26_DD") (pintype "bidirectional"))
    )
    (net (code "153") (name "unconnected-(J4-27-PadEE)") (class "Default")
      (node (ref "J4") (pin "EE") (pinfunction "27_EE") (pintype "bidirectional"))
    )
    (net (code "154") (name "unconnected-(J4-28-PadFF)") (class "Default")
      (node (ref "J4") (pin "FF") (pinfunction "28_FF") (pintype "bidirectional"))
    )
    (net (code "155") (name "unconnected-(J4-29-PadHH)") (class "Default")
      (node (ref "J4") (pin "HH") (pinfunction "29_HH") (pintype "bidirectional"))
    )
    (net (code "156") (name "unconnected-(J4-30-PadJJ)") (class "Default")
      (node (ref "J4") (pin "JJ") (pinfunction "30_JJ") (pintype "bidirectional"))
    )
    (net (code "157") (name "unconnected-(J4-31-PadKK)") (class "Default")
      (node (ref "J4") (pin "KK") (pinfunction "31_KK") (pintype "bidirectional"))
    )
    (net (code "158") (name "unconnected-(J4-32-PadLL)") (class "Default")
      (node (ref "J4") (pin "LL") (pinfunction "32_LL") (pintype "bidirectional"))
    )
    (net (code "159") (name "unconnected-(J4-33-PadMM)") (class "Default")
      (node (ref "J4") (pin "MM") (pinfunction "33_MM") (pintype "bidirectional"))
    )
    (net (code "160") (name "unconnected-(J4-34-PadNN)") (class "Default")
      (node (ref "J4") (pin "NN") (pinfunction "34_NN") (pintype "bidirectional"))
    )
    (net (code "161") (name "unconnected-(J4-35-PadPP)") (class "Default")
      (node (ref "J4") (pin "PP") (pinfunction "35_PP") (pintype "bidirectional"))
    )
    (net (code "162") (name "unconnected-(J4-36-PadRR)") (class "Default")
      (node (ref "J4") (pin "RR") (pinfunction "36_RR") (pintype "bidirectional"))
    )
    (net (code "163") (name "unconnected-(U2-GPA3-Pad24)") (class "Default")
      (node (ref "U2") (pin "24") (pinfunction "GPA3_24") (pintype "bidirectional"))
    )
    (net (code "164") (name "unconnected-(U2-GPA7-Pad28)") (class "Default")
      (node (ref "U2") (pin "28") (pinfunction "GPA7_28") (pintype "bidirectional"))
    )
    (net (code "165") (name "unconnected-(U2-GPB3-Pad4)") (class "Default")
      (node (ref "U2") (pin "4") (pinfunction "GPB3_4") (pintype "bidirectional"))
    )
    (net (code "166") (name "unconnected-(U2-GPB7-Pad8)") (class "Default")
      (node (ref "U2") (pin "8") (pinfunction "GPB7_8") (pintype "bidirectional"))
    )
    (net (code "167") (name "unconnected-(U2-INTA-Pad20)") (class "Default")
      (node (ref "U2") (pin "20") (pinfunction "INTA_20") (pintype "output"))
    )
    (net (code "168") (name "unconnected-(U2-INTB-Pad19)") (class "Default")
      (node (ref "U2") (pin "19") (pinfunction "INTB_19") (pintype "output"))
    )
    (net (code "169") (name "unconnected-(U7D-O-Pad11)") (class "Default")
      (node (ref "U7") (pin "11") (pinfunction "O_11") (pintype "open_collector"))
    )
    (net (code "170") (name "unconnected-(U10A-T1OUT-Pad14)") (class "Default")
      (node (ref "U10") (pin "14") (pinfunction "T1OUT_14") (pintype "output"))
    )
    (net (code "171") (name "~{BDISABLE}") (class "Default")
      (node (ref "E7A") (pin "10") (pinfunction "I1_10") (pintype "input"))
      (node (ref "E7A") (pin "11") (pinfunction "I2_11") (pintype "input"))
      (node (ref "E7A") (pin "13") (pinfunction "I2_13") (pintype "input"))
      (node (ref "E8") (pin "18") (pinfunction "Y1_18") (pintype "tri_state"))
    )
    (net (code "172") (name "~{BMD_DIR}") (class "Default")
      (node (ref "E7A") (pin "3") (pinfunction "I0_3") (pintype "input"))
      (node (ref "E8") (pin "17") (pinfunction "Y2_17") (pintype "tri_state"))
    )
    (net (code "173") (name "~{BREAK_CYCLE}") (class "Default")
      (node (ref "J1") (pin "BL2") (pinfunction "1_BL2") (pintype "bidirectional"))
    )
    (net (code "174") (name "~{BRK_DATA}") (class "Default")
      (node (ref "J1") (pin "BK2") (pinfunction "1_BK2") (pintype "bidirectional"))
      (node (ref "U7") (pin "3") (pinfunction "O_3") (pintype "open_collector"))
    )
    (net (code "175") (name "~{BRK_IN_PROG}") (class "Default")
      (node (ref "J1") (pin "BE2") (pinfunction "1_BE2") (pintype "bidirectional"))
    )
    (net (code "176") (name "~{BSOURCE}") (class "Default")
      (node (ref "E8") (pin "14") (pinfunction "Y5_14") (pintype "tri_state"))
      (node (ref "E8") (pin "7") (pinfunction "A6_7") (pintype "input"))
    )
    (net (code "177") (name "~{BUS_STROBE}") (class "Default")
      (node (ref "J1") (pin "CK1") (pinfunction "1_CK1") (pintype "bidirectional"))
    )
    (net (code "178") (name "~{BWRITE}") (class "Default")
      (node (ref "E8") (pin "16") (pinfunction "Y3_16") (pintype "tri_state"))
      (node (ref "E8") (pin "5") (pinfunction "A4_5") (pintype "input"))
    )
    (net (code "179") (name "~{C0}") (class "Default")
      (node (ref "J1") (pin "CE1") (pinfunction "1_CE1") (pintype "bidirectional"))
    )
    (net (code "180") (name "~{C1}") (class "Default")
      (node (ref "J1") (pin "CH1") (pinfunction "1_CH1") (pintype "bidirectional"))
    )
    (net (code "181") (name "~{C2}") (class "Default")
      (node (ref "J1") (pin "CJ1") (pinfunction "1_CJ1") (pintype "bidirectional"))
    )
    (net (code "182") (name "~{CE}") (class "Default")
      (node (ref "C22") (pin "1") (pinfunction "1_1") (pintype "passive"))
      (node (ref "E3") (pin "20") (pinfunction "~{CE}_20") (pintype "input"))
      (node (ref "E4") (pin "20") (pinfunction "~{CE}_20") (pintype "input"))
      (node (ref "Q3") (pin "1") (pinfunction "C_1") (pintype "passive"))
      (node (ref "R15") (pin "1") (pinfunction "1_1") (pintype "passive"))
    )
    (net (code "183") (name "~{CPMA_DISABLE}") (class "Default")
      (node (ref "J1") (pin "CU1") (pinfunction "1_CU1") (pintype "bidirectional"))
    )
    (net (code "184") (name "~{DATA00}") (class "Default")
      (node (ref "J1") (pin "AR1") (pinfunction "1_AR1") (pintype "bidirectional"))
      (node (ref "U3") (pin "3") (pinfunction "O_3") (pintype "open_collector"))
    )
    (net (code "185") (name "~{DATA01}") (class "Default")
      (node (ref "J1") (pin "AS1") (pinfunction "1_AS1") (pintype "bidirectional"))
      (node (ref "U3") (pin "6") (pinfunction "O_6") (pintype "open_collector"))
    )
    (net (code "186") (name "~{DATA02}") (class "Default")
      (node (ref "J1") (pin "AU1") (pinfunction "1_AU1") (pintype "bidirectional"))
      (node (ref "U3") (pin "11") (pinfunction "O_11") (pintype "open_collector"))
    )
    (net (code "187") (name "~{DATA03}") (class "Default")
      (node (ref "J1") (pin "AV1") (pinfunction "1_AV1") (pintype "bidirectional"))
      (node (ref "U3") (pin "8") (pinfunction "O_8") (pintype "open_collector"))
    )
    (net (code "188") (name "~{DATA04}") (class "Default")
      (node (ref "J1") (pin "BR1") (pinfunction "1_BR1") (pintype "bidirectional"))
      (node (ref "U4") (pin "3") (pinfunction "O_3") (pintype "open_collector"))
    )
    (net (code "189") (name "~{DATA05}") (class "Default")
      (node (ref "J1") (pin "BS1") (pinfunction "1_BS1") (pintype "bidirectional"))
      (node (ref "U4") (pin "6") (pinfunction "O_6") (pintype "open_collector"))
    )
    (net (code "190") (name "~{DATA06}") (class "Default")
      (node (ref "J1") (pin "BU1") (pinfunction "1_BU1") (pintype "bidirectional"))
      (node (ref "U4") (pin "11") (pinfunction "O_11") (pintype "open_collector"))
    )
    (net (code "191") (name "~{DATA07}") (class "Default")
      (node (ref "J1") (pin "BV1") (pinfunction "1_BV1") (pintype "bidirectional"))
      (node (ref "U4") (pin "8") (pinfunction "O_8") (pintype "open_collector"))
    )
    (net (code "192") (name "~{DATA08}") (class "Default")
      (node (ref "J1") (pin "DR1") (pinfunction "1_DR1") (pintype "bidirectional"))
      (node (ref "U5") (pin "3") (pinfunction "O_3") (pintype "open_collector"))
    )
    (net (code "193") (name "~{DATA09}") (class "Default")
      (node (ref "J1") (pin "DS1") (pinfunction "1_DS1") (pintype "bidirectional"))
      (node (ref "U5") (pin "6") (pinfunction "O_6") (pintype "open_collector"))
    )
    (net (code "194") (name "~{DATA10}") (class "Default")
      (node (ref "J1") (pin "DU1") (pinfunction "1_DU1") (pintype "bidirectional"))
      (node (ref "U5") (pin "11") (pinfunction "O_11") (pintype "open_collector"))
    )
    (net (code "195") (name "~{DATA11}") (class "Default")
      (node (ref "J1") (pin "DV1") (pinfunction "1_DV1") (pintype "bidirectional"))
      (node (ref "U5") (pin "8") (pinfunction "O_8") (pintype "open_collector"))
    )
    (net (code "196") (name "~{D}") (class "Default")
      (node (ref "J1") (pin "DK2") (pinfunction "1_DK2") (pintype "bidirectional"))
    )
    (net (code "197") (name "~{EMA0}") (class "Default")
      (node (ref "E3") (pin "8") (pinfunction "A2_8") (pintype "input"))
      (node (ref "E4") (pin "8") (pinfunction "A2_8") (pintype "input"))
      (node (ref "E5") (pin "3") (pinfunction "C_3") (pintype "input"))
      (node (ref "J1") (pin "AD2") (pinfunction "1_AD2") (pintype "bidirectional"))
    )
    (net (code "198") (name "~{EMA1}") (class "Default")
      (node (ref "E3") (pin "9") (pinfunction "A1_9") (pintype "input"))
      (node (ref "E4") (pin "9") (pinfunction "A1_9") (pintype "input"))
      (node (ref "E5") (pin "2") (pinfunction "B_2") (pintype "input"))
      (node (ref "J1") (pin "AE2") (pinfunction "1_AE2") (pintype "bidirectional"))
    )
    (net (code "199") (name "~{EMA2}") (class "Default")
      (node (ref "E3") (pin "10") (pinfunction "A0_10") (pintype "input"))
      (node (ref "E4") (pin "10") (pinfunction "A0_10") (pintype "input"))
      (node (ref "E5") (pin "1") (pinfunction "A_1") (pintype "input"))
      (node (ref "J1") (pin "AH2") (pinfunction "1_AH2") (pintype "bidirectional"))
    )
    (net (code "200") (name "~{E}") (class "Default")
      (node (ref "J1") (pin "DL2") (pinfunction "1_DL2") (pintype "bidirectional"))
    )
    (net (code "201") (name "~{FSET}") (class "Default")
      (node (ref "J1") (pin "DP2") (pinfunction "1_DP2") (pintype "bidirectional"))
    )
    (net (code "202") (name "~{F}") (class "Default")
      (node (ref "J1") (pin "DJ2") (pinfunction "1_DJ2") (pintype "bidirectional"))
    )
    (net (code "203") (name "~{IND1}") (class "Default")
      (node (ref "J1") (pin "CU2") (pinfunction "1_CU2") (pintype "bidirectional"))
    )
    (net (code "204") (name "~{IND2}") (class "Default")
      (node (ref "J1") (pin "CV2") (pinfunction "1_CV2") (pintype "bidirectional"))
    )
    (net (code "205") (name "~{INTERNAL_IO}") (class "Default")
      (node (ref "J1") (pin "CL1") (pinfunction "1_CL1") (pintype "bidirectional"))
    )
    (net (code "206") (name "~{INT_RQST}") (class "Default")
      (node (ref "J1") (pin "CP1") (pinfunction "1_CP1") (pintype "bidirectional"))
    )
    (net (code "207") (name "~{IO_PAUSE}") (class "Default")
      (node (ref "J1") (pin "CD1") (pinfunction "1_CD1") (pintype "bidirectional"))
    )
    (net (code "208") (name "~{IR0}") (class "Default")
      (node (ref "J1") (pin "DD2") (pinfunction "1_DD2") (pintype "bidirectional"))
    )
    (net (code "209") (name "~{IR1}") (class "Default")
      (node (ref "J1") (pin "DE2") (pinfunction "1_DE2") (pintype "bidirectional"))
    )
    (net (code "210") (name "~{IR2}") (class "Default")
      (node (ref "J1") (pin "DH2") (pinfunction "1_DH2") (pintype "bidirectional"))
    )
    (net (code "211") (name "~{KEY_CONT}") (class "Default")
      (node (ref "J1") (pin "DU2") (pinfunction "1_DU2") (pintype "bidirectional"))
      (node (ref "U6") (pin "11") (pinfunction "O_11") (pintype "open_collector"))
    )
    (net (code "212") (name "~{LA_ENABLE}") (class "Default")
      (node (ref "J1") (pin "BM2") (pinfunction "1_BM2") (pintype "bidirectional"))
      (node (ref "U6") (pin "6") (pinfunction "O_6") (pintype "open_collector"))
    )
    (net (code "213") (name "~{LINK_DATA}") (class "Default")
      (node (ref "J1") (pin "CR2") (pinfunction "1_CR2") (pintype "bidirectional"))
    )
    (net (code "214") (name "~{LINK_LOAD}") (class "Default")
      (node (ref "J1") (pin "CS2") (pinfunction "1_CS2") (pintype "bidirectional"))
    )
    (net (code "215") (name "~{LINK}") (class "Default")
      (node (ref "J1") (pin "AV2") (pinfunction "1_AV2") (pintype "bidirectional"))
    )
    (net (code "216") (name "~{LOAD_CONT}") (class "Default")
      (node (ref "J1") (pin "BH2") (pinfunction "1_BH2") (pintype "bidirectional"))
    )
    (net (code "217") (name "~{MA00}") (class "Default")
      (node (ref "E3") (pin "21") (pinfunction "A10_21") (pintype "input"))
      (node (ref "E4") (pin "21") (pinfunction "A10_21") (pintype "input"))
      (node (ref "J1") (pin "AD1") (pinfunction "1_AD1") (pintype "bidirectional"))
    )
    (net (code "218") (name "~{MA01}") (class "Default")
      (node (ref "E3") (pin "23") (pinfunction "A11_23") (pintype "input"))
      (node (ref "E4") (pin "23") (pinfunction "A11_23") (pintype "input"))
      (node (ref "J1") (pin "AE1") (pinfunction "1_AE1") (pintype "bidirectional"))
    )
    (net (code "219") (name "~{MA02}") (class "Default")
      (node (ref "E3") (pin "24") (pinfunction "A9_24") (pintype "input"))
      (node (ref "E4") (pin "24") (pinfunction "A9_24") (pintype "input"))
      (node (ref "J1") (pin "AH1") (pinfunction "1_AH1") (pintype "bidirectional"))
    )
    (net (code "220") (name "~{MA03}") (class "Default")
      (node (ref "E3") (pin "25") (pinfunction "A8_25") (pintype "input"))
      (node (ref "E4") (pin "25") (pinfunction "A8_25") (pintype "input"))
      (node (ref "J1") (pin "AJ1") (pinfunction "1_AJ1") (pintype "bidirectional"))
    )
    (net (code "221") (name "~{MA04}") (class "Default")
      (node (ref "E3") (pin "26") (pinfunction "A13_26") (pintype "input"))
      (node (ref "E4") (pin "26") (pinfunction "A13_26") (pintype "input"))
      (node (ref "J1") (pin "BD1") (pinfunction "1_BD1") (pintype "bidirectional"))
    )
    (net (code "222") (name "~{MA05}") (class "Default")
      (node (ref "E3") (pin "1") (pinfunction "A14_1") (pintype "input"))
      (node (ref "E4") (pin "1") (pinfunction "A14_1") (pintype "input"))
      (node (ref "J1") (pin "BE1") (pinfunction "1_BE1") (pintype "bidirectional"))
    )
    (net (code "223") (name "~{MA06}") (class "Default")
      (node (ref "E3") (pin "2") (pinfunction "A12_2") (pintype "input"))
      (node (ref "E4") (pin "2") (pinfunction "A12_2") (pintype "input"))
      (node (ref "J1") (pin "BH1") (pinfunction "1_BH1") (pintype "bidirectional"))
    )
    (net (code "224") (name "~{MA07}") (class "Default")
      (node (ref "E3") (pin "3") (pinfunction "A7_3") (pintype "input"))
      (node (ref "E4") (pin "3") (pinfunction "A7_3") (pintype "input"))
      (node (ref "J1") (pin "BJ1") (pinfunction "1_BJ1") (pintype "bidirectional"))
    )
    (net (code "225") (name "~{MA08}") (class "Default")
      (node (ref "E3") (pin "4") (pinfunction "A6_4") (pintype "input"))
      (node (ref "E4") (pin "4") (pinfunction "A6_4") (pintype "input"))
      (node (ref "J1") (pin "DD1") (pinfunction "1_DD1") (pintype "bidirectional"))
    )
    (net (code "226") (name "~{MA09}") (class "Default")
      (node (ref "E3") (pin "5") (pinfunction "A5_5") (pintype "input"))
      (node (ref "E4") (pin "5") (pinfunction "A5_5") (pintype "input"))
      (node (ref "J1") (pin "DE1") (pinfunction "1_DE1") (pintype "bidirectional"))
    )
    (net (code "227") (name "~{MA10}") (class "Default")
      (node (ref "E3") (pin "6") (pinfunction "A4_6") (pintype "input"))
      (node (ref "E4") (pin "6") (pinfunction "A4_6") (pintype "input"))
      (node (ref "J1") (pin "DH1") (pinfunction "1_DH1") (pintype "bidirectional"))
    )
    (net (code "228") (name "~{MA11}") (class "Default")
      (node (ref "E3") (pin "7") (pinfunction "A3_7") (pintype "input"))
      (node (ref "E4") (pin "7") (pinfunction "A3_7") (pintype "input"))
      (node (ref "J1") (pin "DJ1") (pinfunction "1_DJ1") (pintype "bidirectional"))
    )
    (net (code "229") (name "~{MD00}") (class "Default")
      (node (ref "E1") (pin "2") (pinfunction "A1_2") (pintype "bidirectional"))
      (node (ref "J1") (pin "AK1") (pinfunction "1_AK1") (pintype "bidirectional"))
    )
    (net (code "230") (name "~{MD01}") (class "Default")
      (node (ref "E1") (pin "3") (pinfunction "A2_3") (pintype "bidirectional"))
      (node (ref "J1") (pin "AL1") (pinfunction "1_AL1") (pintype "bidirectional"))
    )
    (net (code "231") (name "~{MD02}") (class "Default")
      (node (ref "E1") (pin "4") (pinfunction "A3_4") (pintype "bidirectional"))
      (node (ref "J1") (pin "AM1") (pinfunction "1_AM1") (pintype "bidirectional"))
    )
    (net (code "232") (name "~{MD03}") (class "Default")
      (node (ref "E1") (pin "5") (pinfunction "A4_5") (pintype "bidirectional"))
      (node (ref "J1") (pin "AP1") (pinfunction "1_AP1") (pintype "bidirectional"))
    )
    (net (code "233") (name "~{MD04}") (class "Default")
      (node (ref "E2") (pin "2") (pinfunction "A1_2") (pintype "bidirectional"))
      (node (ref "J1") (pin "BK1") (pinfunction "1_BK1") (pintype "bidirectional"))
    )
    (net (code "234") (name "~{MD05}") (class "Default")
      (node (ref "E2") (pin "3") (pinfunction "A2_3") (pintype "bidirectional"))
      (node (ref "J1") (pin "BL1") (pinfunction "1_BL1") (pintype "bidirectional"))
    )
    (net (code "235") (name "~{MD06}") (class "Default")
      (node (ref "E2") (pin "4") (pinfunction "A3_4") (pintype "bidirectional"))
      (node (ref "J1") (pin "BM1") (pinfunction "1_BM1") (pintype "bidirectional"))
    )
    (net (code "236") (name "~{MD07}") (class "Default")
      (node (ref "E2") (pin "5") (pinfunction "A4_5") (pintype "bidirectional"))
      (node (ref "J1") (pin "BP1") (pinfunction "1_BP1") (pintype "bidirectional"))
    )
    (net (code "237") (name "~{MD08}") (class "Default")
      (node (ref "E2") (pin "6") (pinfunction "A5_6") (pintype "bidirectional"))
      (node (ref "J1") (pin "DK1") (pinfunction "1_DK1") (pintype "bidirectional"))
    )
    (net (code "238") (name "~{MD09}") (class "Default")
      (node (ref "E2") (pin "7") (pinfunction "A6_7") (pintype "bidirectional"))
      (node (ref "J1") (pin "DL1") (pinfunction "1_DL1") (pintype "bidirectional"))
    )
    (net (code "239") (name "~{MD10}") (class "Default")
      (node (ref "E2") (pin "8") (pinfunction "A7_8") (pintype "bidirectional"))
      (node (ref "J1") (pin "DM1") (pinfunction "1_DM1") (pintype "bidirectional"))
    )
    (net (code "240") (name "~{MD11}") (class "Default")
      (node (ref "E2") (pin "9") (pinfunction "A8_9") (pintype "bidirectional"))
      (node (ref "J1") (pin "DP1") (pinfunction "1_DP1") (pintype "bidirectional"))
    )
    (net (code "241") (name "~{MD_DIR}") (class "Default")
      (node (ref "E8") (pin "8") (pinfunction "A7_8") (pintype "input"))
      (node (ref "J1") (pin "AK2") (pinfunction "1_AK2") (pintype "bidirectional"))
      (node (ref "U7") (pin "6") (pinfunction "O_6") (pintype "open_collector"))
    )
    (net (code "242") (name "~{MEM_START}") (class "Default")
      (node (ref "J1") (pin "AJ2") (pinfunction "1_AJ2") (pintype "bidirectional"))
      (node (ref "U6") (pin "3") (pinfunction "O_3") (pintype "open_collector"))
    )
    (net (code "243") (name "~{MS_DISABLE}") (class "Default")
      (node (ref "J1") (pin "CV1") (pinfunction "1_CV1") (pintype "bidirectional"))
      (node (ref "U6") (pin "8") (pinfunction "O_8") (pintype "open_collector"))
    )
    (net (code "244") (name "~{NOT_LAST_TR}") (class "Default")
      (node (ref "J1") (pin "CM1") (pinfunction "1_CM1") (pintype "bidirectional"))
    )
    (net (code "245") (name "~{NTS_STALL}") (class "Default")
      (node (ref "J1") (pin "BR2") (pinfunction "1_BR2") (pintype "bidirectional"))
    )
    (net (code "246") (name "~{OVERFLOW}") (class "Default")
      (node (ref "J1") (pin "BJ2") (pinfunction "1_BJ2") (pintype "bidirectional"))
    )
    (net (code "247") (name "~{READ_EN}") (class "Default")
      (node (ref "E3") (pin "22") (pinfunction "~{OE}_22") (pintype "input"))
      (node (ref "E4") (pin "22") (pinfunction "~{OE}_22") (pintype "input"))
      (node (ref "E7A") (pin "8") (pinfunction "O_8") (pintype "output"))
    )
    (net (code "248") (name "~{RESET}") (class "Default")
      (node (ref "C11") (pin "1") (pinfunction "1_1") (pintype "passive"))
      (node (ref "D1") (pin "A") (pinfunction "A_A") (pintype "passive"))
      (node (ref "J3") (pin "5") (pinfunction "5_5") (pintype "passive"))
      (node (ref "R19") (pin "1") (pinfunction "1_1") (pintype "passive"))
      (node (ref "U1") (pin "1") (pinfunction "PC6(/RESET)_1") (pintype "bidirectional"))
    )
    (net (code "249") (name "~{ROM_ADDR}") (class "Default")
      (node (ref "E5") (pin "6") (pinfunction "G1_6") (pintype "input"))
      (node (ref "J1") (pin "AU2") (pinfunction "1_AU2") (pintype "bidirectional"))
    )
    (net (code "250") (name "~{RUN}") (class "Default")
      (node (ref "J1") (pin "BU2") (pinfunction "1_BU2") (pintype "bidirectional"))
      (node (ref "R2") (pin "2") (pinfunction "2_2") (pintype "passive"))
    )
    (net (code "251") (name "~{SKIP}") (class "Default")
      (node (ref "J1") (pin "CS1") (pinfunction "1_CS1") (pintype "bidirectional"))
    )
    (net (code "252") (name "~{STOP}") (class "Default")
      (node (ref "J1") (pin "DS2") (pinfunction "1_DS2") (pintype "bidirectional"))
      (node (ref "U7") (pin "8") (pinfunction "O_8") (pintype "open_collector"))
    )
    (net (code "253") (name "~{TS1}") (class "Default")
      (node (ref "J1") (pin "CK2") (pinfunction "1_CK2") (pintype "bidirectional"))
    )
    (net (code "254") (name "~{TS2}") (class "Default")
      (node (ref "J1") (pin "CL2") (pinfunction "1_CL2") (pintype "bidirectional"))
    )
    (net (code "255") (name "~{TS3}") (class "Default")
      (node (ref "J1") (pin "CM2") (pinfunction "1_CM2") (pintype "bidirectional"))
    )
    (net (code "256") (name "~{TS4}") (class "Default")
      (node (ref "J1") (pin "CP2") (pinfunction "1_CP2") (pintype "bidirectional"))
      (node (ref "U8") (pin "13") (pinfunction "I2_13") (pintype "input"))
    )
    (net (code "257") (name "~{USER_MODE}") (class "Default")
      (node (ref "J1") (pin "DM2") (pinfunction "1_DM2") (pintype "bidirectional"))
    )
    (net (code "258") (name "~{WRITE_EN}") (class "Default")
      (node (ref "E3") (pin "27") (pinfunction "~{WE}_27") (pintype "input"))
      (node (ref "E4") (pin "27") (pinfunction "~{WE}_27") (pintype "input"))
      (node (ref "E7A") (pin "1") (pinfunction "I0_1") (pintype "input"))
      (node (ref "E7A") (pin "2") (pinfunction "I1_2") (pintype "input"))
      (node (ref "E7A") (pin "6") (pinfunction "O_6") (pintype "output"))
    )
    (net (code "259") (name "~{W_KEY_CONTROL}") (class "Default")
      (node (ref "U1") (pin "13") (pinfunction "PD7(AIN1)_13") (pintype "bidirectional"))
      (node (ref "U6") (pin "12") (pinfunction "I0_12") (pintype "input"))
    )
    (net (code "260") (name "~{W_LA_ENABLE}") (class "Default")
      (node (ref "U1") (pin "11") (pinfunction "PD5(T1)_11") (pintype "bidirectional"))
      (node (ref "U6") (pin "4") (pinfunction "I0_4") (pintype "input"))
    )
    (net (code "261") (name "~{W_MEM_START}") (class "Default")
      (node (ref "R7") (pin "2") (pinfunction "2_2") (pintype "passive"))
      (node (ref "U1") (pin "25") (pinfunction "PC2(ADC2)_25") (pintype "bidirectional"))
      (node (ref "U6") (pin "1") (pinfunction "I0_1") (pintype "input"))
      (node (ref "U6") (pin "2") (pinfunction "I1_2") (pintype "input"))
    )
    (net (code "262") (name "~{W_MS_IR_DISABLE}") (class "Default")
      (node (ref "U1") (pin "12") (pinfunction "PD6(AIN0)_12") (pintype "bidirectional"))
      (node (ref "U6") (pin "9") (pinfunction "I0_9") (pintype "input"))
    )
  )
)
